# ETH_CAN_Sheet1.net
KiCad netlist of a schematic drawn in Altium Designer
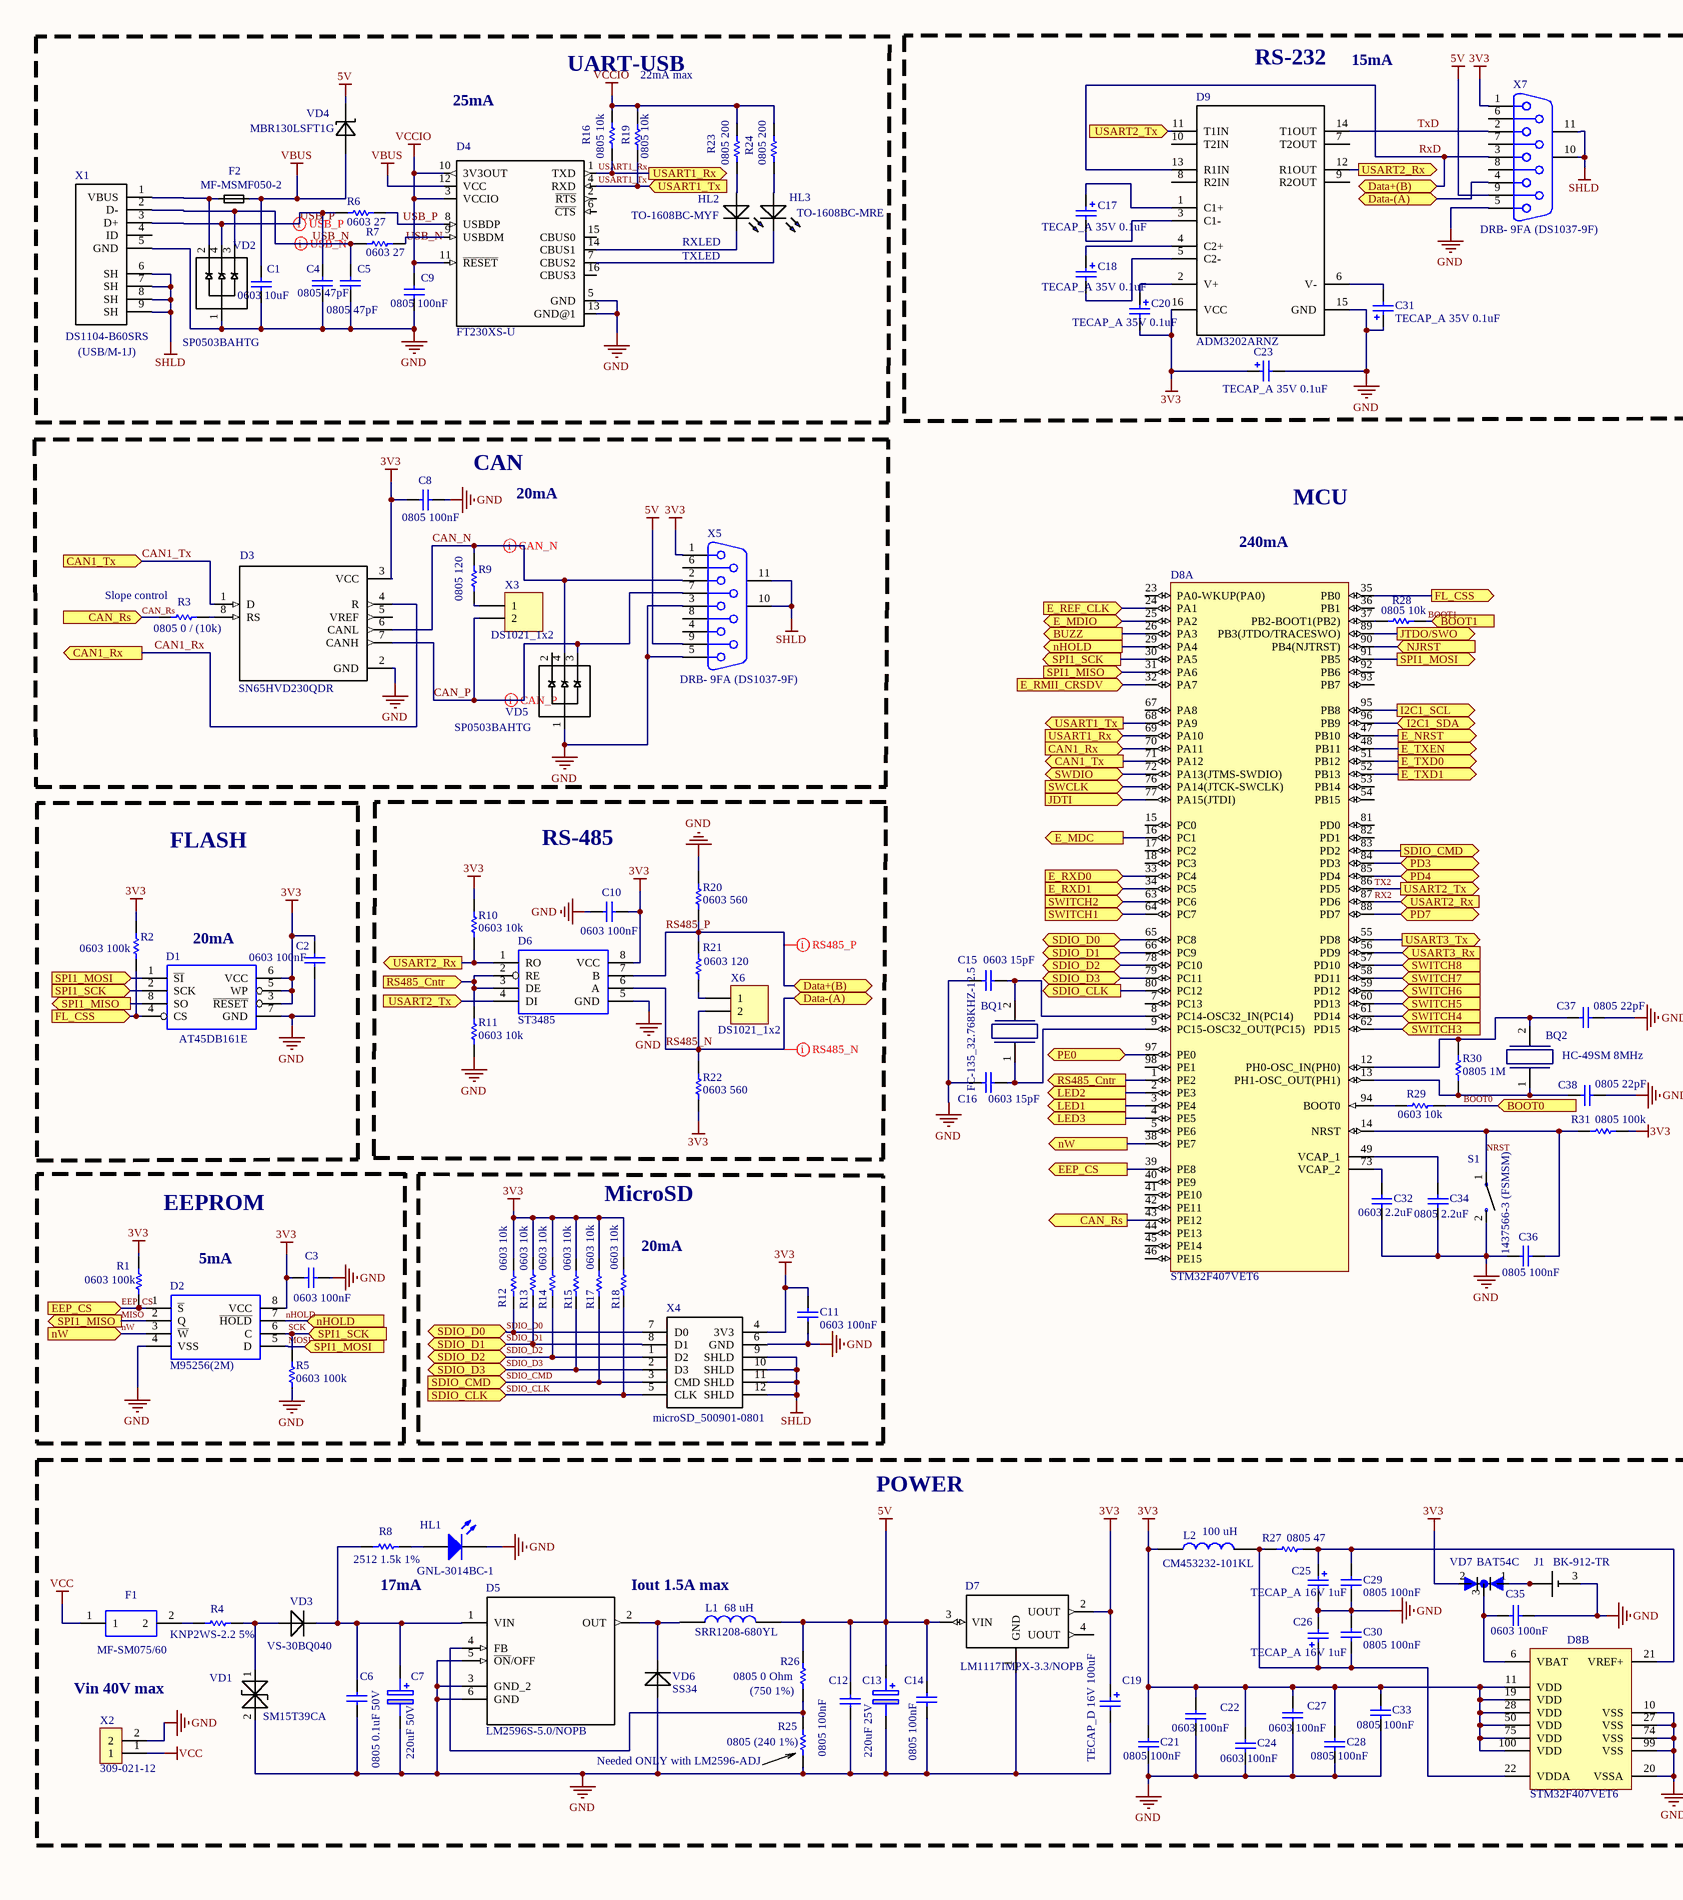
[diagram p0: ETH_CAN_Sheet1.SchDoc, left]
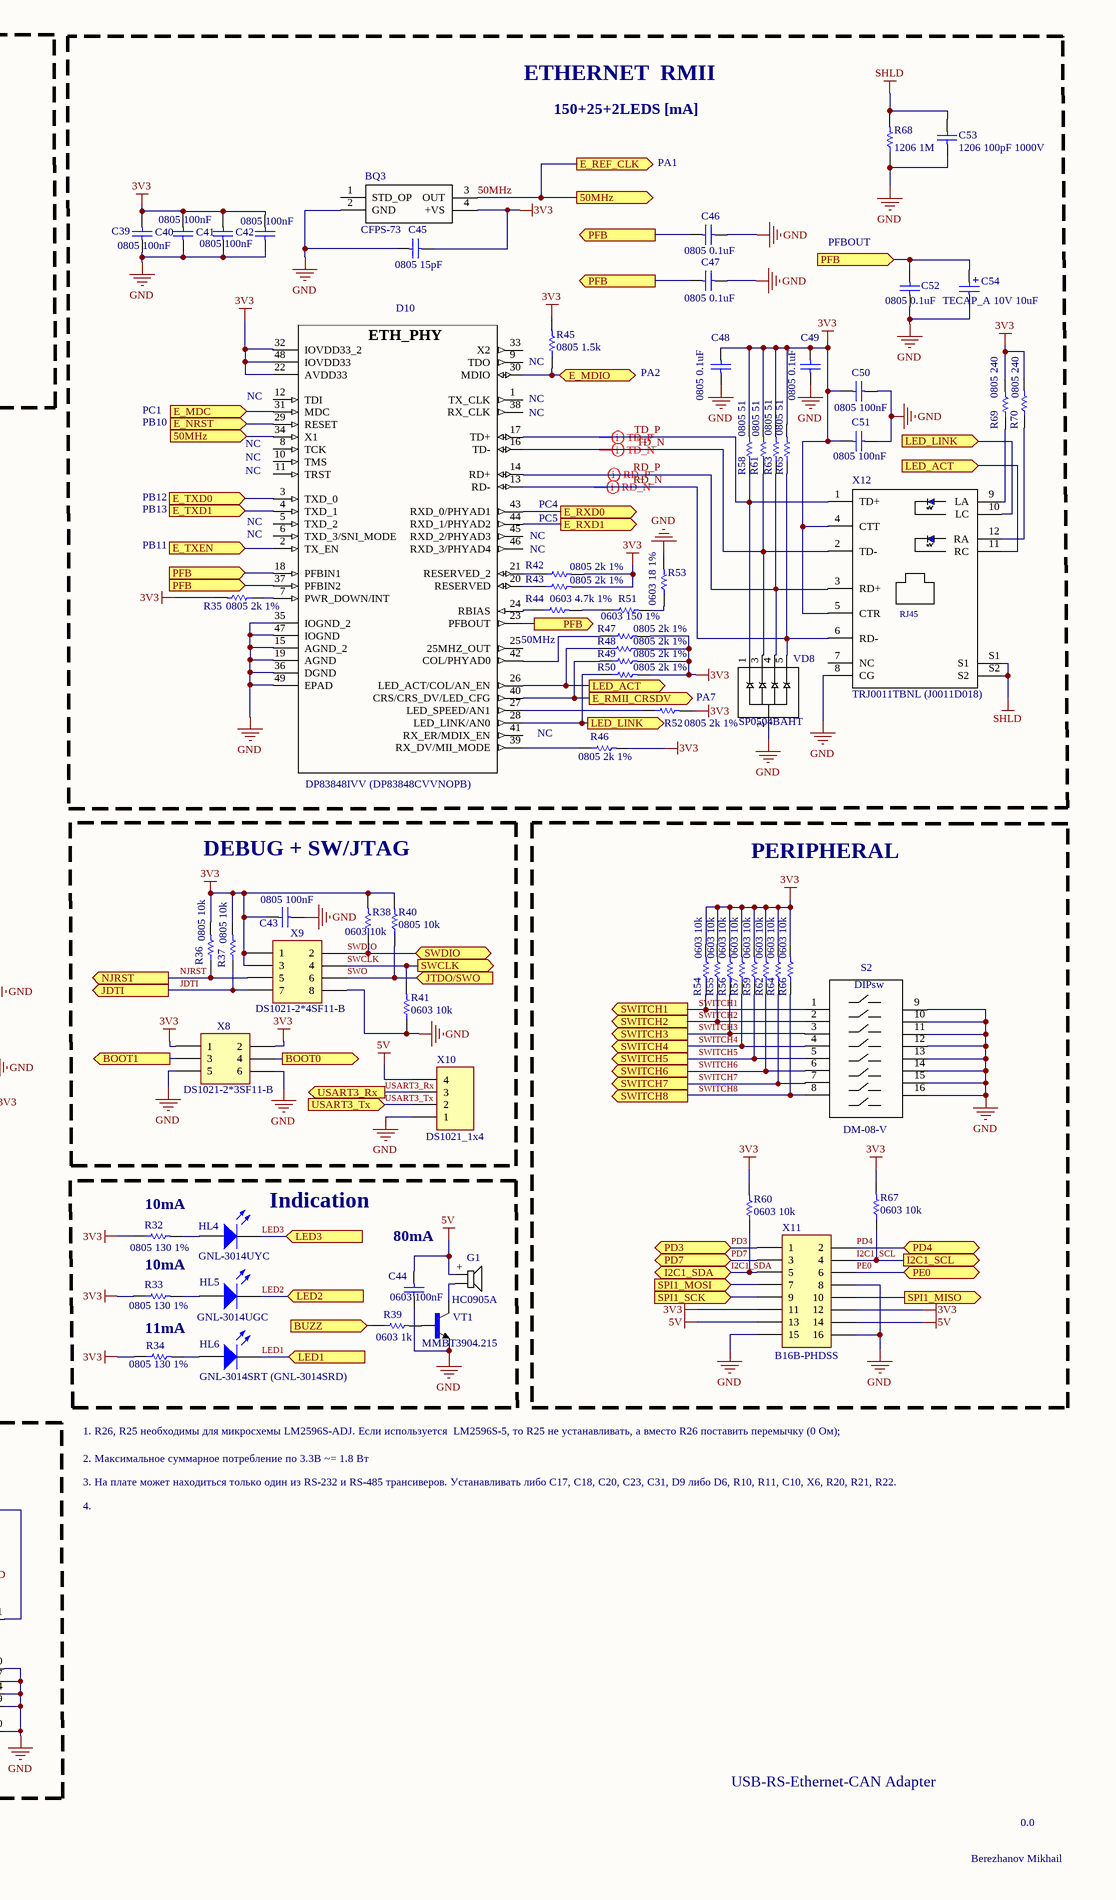
[diagram p1: ETH_CAN_Sheet1.SchDoc, right]

(export (version "E")
  (design (tool "Eeschema 10.0.6"))
  (components
    (comp (ref "BQ1")
      (value "FC-135_32.768KHZ-12.5")
      (footprint "FC-135")
      (description "Clock SMD Crystal")
      (libsource (lib "MyCompLib") (part "FC135-32768-7"))
    )
    (comp (ref "BQ2")
      (value "HC-49SM 8MHz")
      (footprint "HC49SM")
      (description "HC49SM")
      (libsource (lib "MyCompLib") (part "HC49SM"))
    )
    (comp (ref "BQ3")
      (value "CFPS-73")
      (footprint "CFPS-73")
      (description "IQD FREQUENCY PRODUCTS - SPXO018044-CFPS-73 - OSCILLATOR FREQUENCY, 50MHZ")
      (libsource (lib "MyCompLib") (part "SPXO018044CFPS-73"))
    )
    (comp (ref "C1")
      (value "0603 10uF")
      (footprint "C_SMD0603")
      (description "SMD Cap 0603")
      (libsource (lib "MyCompLib") (part "C0603"))
    )
    (comp (ref "C2")
      (value "0603 100nF")
      (footprint "C_SMD0603")
      (description "SMD Cap 0603")
      (libsource (lib "MyCompLib") (part "C0603"))
    )
    (comp (ref "C3")
      (value "0603 100nF")
      (footprint "C_SMD0603")
      (description "SMD Cap 0603")
      (libsource (lib "MyCompLib") (part "C0603"))
    )
    (comp (ref "C4")
      (value "0805 47pF")
      (footprint "C_SMD0805")
      (description "SMD Cap 0805")
      (fields (field (name "PUBLISHER") "Altium Limited"))
      (libsource (lib "MyCompLib") (part "C0805"))
    )
    (comp (ref "C5")
      (value "0805 47pF")
      (footprint "C_SMD0805")
      (description "SMD Cap 0805")
      (fields (field (name "PUBLISHER") "Altium Limited"))
      (libsource (lib "MyCompLib") (part "C0805"))
    )
    (comp (ref "C6")
      (value "0805 0.1uF 50V")
      (footprint "C_SMD0805")
      (description "SMD Cap 0805")
      (fields (field (name "PUBLISHER") "Altium Limited"))
      (libsource (lib "MyCompLib") (part "C0805"))
    )
    (comp (ref "C7")
      (value "220uF 50V")
      (footprint "SMD_ELC_CAP")
      (fields
        (field (name "MANUFACTURER_PART_NUMBER") "EEEFK1H221P")
        (field (name "RS PART NUMBER") "6294598")
      )
      (libsource (lib "MyCompLib") (part "EEEFK1H221P"))
    )
    (comp (ref "C8")
      (value "0805 100nF")
      (footprint "C_SMD0805")
      (description "SMD Cap 0805")
      (fields (field (name "PUBLISHER") "Altium Limited"))
      (libsource (lib "MyCompLib") (part "C0805"))
    )
    (comp (ref "C9")
      (value "0805 100nF")
      (footprint "C_SMD0805")
      (description "SMD Cap 0805")
      (fields (field (name "PUBLISHER") "Altium Limited"))
      (libsource (lib "MyCompLib") (part "C0805"))
    )
    (comp (ref "C10")
      (value "0603 100nF")
      (footprint "C_SMD0603")
      (description "SMD Cap 0603")
      (libsource (lib "MyCompLib") (part "C0603"))
    )
    (comp (ref "C11")
      (value "0603 100nF")
      (footprint "C_SMD0603")
      (description "SMD Cap 0603")
      (libsource (lib "MyCompLib") (part "C0603"))
    )
    (comp (ref "C12")
      (value "0805 100nF")
      (footprint "C_SMD0805")
      (description "SMD Cap 0805")
      (fields (field (name "PUBLISHER") "Altium Limited"))
      (libsource (lib "MyCompLib") (part "C0805"))
    )
    (comp (ref "C13")
      (value "220uF 25V")
      (footprint "SMD_ELC_CAP")
      (fields
        (field (name "MANUFACTURER_PART_NUMBER") "EEEFK1H221P")
        (field (name "RS PART NUMBER") "6294598")
      )
      (libsource (lib "MyCompLib") (part "EEEFK1H221P"))
    )
    (comp (ref "C14")
      (value "0805 100nF")
      (footprint "C_SMD0805")
      (description "SMD Cap 0805")
      (libsource (lib "") (part "C0805_1"))
    )
    (comp (ref "C15")
      (value "0603 15pF")
      (footprint "C_SMD0603")
      (description "SMD Cap 0603")
      (libsource (lib "MyCompLib") (part "C0603"))
    )
    (comp (ref "C16")
      (value "0603 15pF")
      (footprint "C_SMD0603")
      (description "SMD Cap 0603")
      (libsource (lib "MyCompLib") (part "C0603"))
    )
    (comp (ref "C17")
      (value "TECAP_A 35V 0.1uF")
      (footprint "TECAP_A")
      (description "Tantalum pol cap type A")
      (libsource (lib "MyCompLib") (part "TECAP_A"))
    )
    (comp (ref "C18")
      (value "TECAP_A 35V 0.1uF")
      (footprint "TECAP_A")
      (description "Tantalum pol cap type A")
      (libsource (lib "MyCompLib") (part "TECAP_A"))
    )
    (comp (ref "C19")
      (value "TECAP_D 16V 100uF")
      (footprint "TECAP_D")
      (description "Tantalum pol cap type D")
      (libsource (lib "MyCompLib") (part "TECAP_D"))
    )
    (comp (ref "C20")
      (value "TECAP_A 35V 0.1uF")
      (footprint "TECAP_A")
      (description "Tantalum pol cap type A")
      (libsource (lib "MyCompLib") (part "TECAP_A"))
    )
    (comp (ref "C21")
      (value "0805 100nF")
      (footprint "C_SMD0805")
      (description "SMD Cap 0805")
      (fields (field (name "PUBLISHER") "Altium Limited"))
      (libsource (lib "MyCompLib") (part "C0805"))
    )
    (comp (ref "C22")
      (value "0603 100nF")
      (footprint "C_SMD0603")
      (description "SMD Cap 0603")
      (libsource (lib "MyCompLib") (part "C0603"))
    )
    (comp (ref "C23")
      (value "TECAP_A 35V 0.1uF")
      (footprint "TECAP_A")
      (description "Tantalum pol cap type A")
      (libsource (lib "MyCompLib") (part "TECAP_A"))
    )
    (comp (ref "C24")
      (value "0603 100nF")
      (footprint "C_SMD0603")
      (description "SMD Cap 0603")
      (libsource (lib "MyCompLib") (part "C0603"))
    )
    (comp (ref "C25")
      (value "TECAP_A 16V 1uF")
      (footprint "TECAP_A")
      (description "Tantalum pol cap type A")
      (libsource (lib "MyCompLib") (part "TECAP_A"))
    )
    (comp (ref "C26")
      (value "TECAP_A 16V 1uF")
      (footprint "TECAP_A")
      (description "Tantalum pol cap type A")
      (libsource (lib "MyCompLib") (part "TECAP_A"))
    )
    (comp (ref "C27")
      (value "0603 100nF")
      (footprint "C_SMD0603")
      (description "SMD Cap 0603")
      (libsource (lib "MyCompLib") (part "C0603"))
    )
    (comp (ref "C28")
      (value "0805 100nF")
      (footprint "C_SMD0805")
      (description "SMD Cap 0805")
      (fields (field (name "PUBLISHER") "Altium Limited"))
      (libsource (lib "MyCompLib") (part "C0805"))
    )
    (comp (ref "C29")
      (value "0805 100nF")
      (footprint "C_SMD0805")
      (description "SMD Cap 0805")
      (fields (field (name "PUBLISHER") "Altium Limited"))
      (libsource (lib "MyCompLib") (part "C0805"))
    )
    (comp (ref "C30")
      (value "0805 100nF")
      (footprint "C_SMD0805")
      (description "SMD Cap 0805")
      (fields (field (name "PUBLISHER") "Altium Limited"))
      (libsource (lib "MyCompLib") (part "C0805"))
    )
    (comp (ref "C31")
      (value "TECAP_A 35V 0.1uF")
      (footprint "TECAP_A")
      (description "Tantalum pol cap type A")
      (libsource (lib "MyCompLib") (part "TECAP_A"))
    )
    (comp (ref "C32")
      (value "0603 2.2uF")
      (footprint "C_SMD0603")
      (description "SMD Cap 0603")
      (libsource (lib "MyCompLib") (part "C0603"))
    )
    (comp (ref "C33")
      (value "0805 100nF")
      (footprint "C_SMD0805")
      (description "SMD Cap 0805")
      (fields (field (name "PUBLISHER") "Altium Limited"))
      (libsource (lib "MyCompLib") (part "C0805"))
    )
    (comp (ref "C34")
      (value "0805 2.2uF")
      (footprint "C_SMD0805")
      (description "SMD Cap 0805")
      (fields (field (name "PUBLISHER") "Altium Limited"))
      (libsource (lib "MyCompLib") (part "C0805"))
    )
    (comp (ref "C35")
      (value "0603 100nF")
      (footprint "C_SMD0603")
      (description "SMD Cap 0603")
      (libsource (lib "MyCompLib") (part "C0603"))
    )
    (comp (ref "C36")
      (value "0805 100nF")
      (footprint "C_SMD0805")
      (description "SMD Cap 0805")
      (fields (field (name "PUBLISHER") "Altium Limited"))
      (libsource (lib "MyCompLib") (part "C0805"))
    )
    (comp (ref "C37")
      (value "0805 22pF")
      (footprint "C_SMD0805")
      (description "SMD Cap 0805")
      (fields (field (name "PUBLISHER") "Altium Limited"))
      (libsource (lib "MyCompLib") (part "C0805"))
    )
    (comp (ref "C38")
      (value "0805 22pF")
      (footprint "C_SMD0805")
      (description "SMD Cap 0805")
      (fields (field (name "PUBLISHER") "Altium Limited"))
      (libsource (lib "MyCompLib") (part "C0805"))
    )
    (comp (ref "C39")
      (value "0805 100nF")
      (footprint "C_SMD0805")
      (description "SMD Cap 0805")
      (fields (field (name "PUBLISHER") "Altium Limited"))
      (libsource (lib "MyCompLib") (part "C0805"))
    )
    (comp (ref "C40")
      (value "0805 100nF")
      (footprint "C_SMD0805")
      (description "SMD Cap 0805")
      (fields (field (name "PUBLISHER") "Altium Limited"))
      (libsource (lib "MyCompLib") (part "C0805"))
    )
    (comp (ref "C41")
      (value "0805 100nF")
      (footprint "C_SMD0805")
      (description "SMD Cap 0805")
      (fields (field (name "PUBLISHER") "Altium Limited"))
      (libsource (lib "MyCompLib") (part "C0805"))
    )
    (comp (ref "C42")
      (value "0805 100nF")
      (footprint "C_SMD0805")
      (description "SMD Cap 0805")
      (fields (field (name "PUBLISHER") "Altium Limited"))
      (libsource (lib "MyCompLib") (part "C0805"))
    )
    (comp (ref "C43")
      (value "0805 100nF")
      (footprint "C_SMD0805")
      (description "SMD Cap 0805")
      (fields (field (name "PUBLISHER") "Altium Limited"))
      (libsource (lib "MyCompLib") (part "C0805"))
    )
    (comp (ref "C44")
      (value "0603 100nF")
      (footprint "C_SMD0603")
      (description "SMD Cap 0603")
      (libsource (lib "MyCompLib") (part "C0603"))
    )
    (comp (ref "C45")
      (value "0805 15pF")
      (footprint "C_SMD0805")
      (description "SMD Cap 0805")
      (fields (field (name "PUBLISHER") "Altium Limited"))
      (libsource (lib "MyCompLib") (part "C0805"))
    )
    (comp (ref "C46")
      (value "0805 0.1uF")
      (footprint "C_SMD0805")
      (description "SMD Cap 0805")
      (fields (field (name "PUBLISHER") "Altium Limited"))
      (libsource (lib "MyCompLib") (part "C0805"))
    )
    (comp (ref "C47")
      (value "0805 0.1uF")
      (footprint "C_SMD0805")
      (description "SMD Cap 0805")
      (fields (field (name "PUBLISHER") "Altium Limited"))
      (libsource (lib "MyCompLib") (part "C0805"))
    )
    (comp (ref "C48")
      (value "0805 0.1uF")
      (footprint "C_SMD0805")
      (description "SMD Cap 0805")
      (fields (field (name "PUBLISHER") "Altium Limited"))
      (libsource (lib "MyCompLib") (part "C0805"))
    )
    (comp (ref "C49")
      (value "0805 0.1uF")
      (footprint "C_SMD0805")
      (description "SMD Cap 0805")
      (fields (field (name "PUBLISHER") "Altium Limited"))
      (libsource (lib "MyCompLib") (part "C0805"))
    )
    (comp (ref "C50")
      (value "0805 100nF")
      (footprint "C_SMD0805")
      (description "SMD Cap 0805")
      (fields (field (name "PUBLISHER") "Altium Limited"))
      (libsource (lib "MyCompLib") (part "C0805"))
    )
    (comp (ref "C51")
      (value "0805 100nF")
      (footprint "C_SMD0805")
      (description "SMD Cap 0805")
      (fields (field (name "PUBLISHER") "Altium Limited"))
      (libsource (lib "MyCompLib") (part "C0805"))
    )
    (comp (ref "C52")
      (value "0805 0.1uF")
      (footprint "C_SMD0805")
      (description "SMD Cap 0805")
      (fields (field (name "PUBLISHER") "Altium Limited"))
      (libsource (lib "MyCompLib") (part "C0805"))
    )
    (comp (ref "C53")
      (value "1206 100pF 1000V")
      (footprint "CAP SMD1206")
      (description "SMD Cap 1206")
      (fields (field (name "PUBLISHER") "Altium Limited"))
      (libsource (lib "MyCompLib") (part "C1206"))
    )
    (comp (ref "C54")
      (value "TECAP_A 10V 10uF")
      (footprint "TECAP_A")
      (description "Tantalum pol cap type A")
      (libsource (lib "MyCompLib") (part "TECAP_A"))
    )
    (comp (ref "D1")
      (value "AT45DB161E")
      (footprint "SOIC8(5.3mm)")
      (description "SPI FLASH 16Mbit(528 bytes x 4096 pages)")
      (libsource (lib "MyCompLib") (part "AT45DB161E"))
    )
    (comp (ref "D2")
      (value "M95256(2M)")
      (footprint "SOIC8 (SO-8)")
      (description "M95256-WMN6TP, Serial EEPROM Memory 256kbit, Serial-SPI, 60ns 2.5  5.5 V, 8-Pin SOIC")
      (libsource (lib "MyCompLib") (part "M95256(2M)-WMN6TP"))
    )
    (comp (ref "D3")
      (value "SN65HVD230QDR")
      (footprint "SOIC-12")
      (description "3.3-V CAN Transceiver with Standby Mode 8-SOIC -40 to 125")
      (fields (field (name "MF") "Texas Instruments"))
      (libsource (lib "MyCompLib") (part "SN65HVD230QDR"))
    )
    (comp (ref "D4")
      (value "FT230XS-U")
      (footprint "SSOP16")
      (description "FT230XS-U, USB Controller, 3MBd, USB 1.1, USB 2.0, 5 V, 16-Pin SSOP")
      (fields (field (name "MF") "FTDI,"))
      (libsource (lib "MyCompLib") (part "FT230XS-U"))
    )
    (comp (ref "D5")
      (value "LM2596S-5.0/NOPB")
      (footprint "TO263-5")
      (description "SIMPLE SWITCHER&#174; 4.5V to 40V, 3A Low Component Count Step-Down Regulator")
      (libsource (lib "MyCompLib") (part "LM2596S"))
    )
    (comp (ref "D6")
      (value "ST3485")
      (footprint "SOIC8 (SO-8)")
      (description "3.3 V low power transceiver for RS-485")
      (libsource (lib "MyCompLib") (part "ST3485"))
    )
    (comp (ref "D7")
      (value "LM1117IMPX-3.3/NOPB")
      (footprint "SOT223")
      (description "Линейный регулятор с низким падением напряжения, 3.3В")
      (libsource (lib "MyCompLib") (part "LM1117-3.3"))
    )
    (comp (ref "D8")
      (value "STM32F407VET6")
      (footprint "STM-LQFP100_N")
      (fields (field (name "MANUFACTURER") "STMicroelectronics"))
      (libsource (lib "STMicroelectronics STM32 F4") (part "STM32F407VET6"))
    )
    (comp (ref "D9")
      (value "ADM3202ARNZ")
      (footprint "SOIC-16")
      (description "3.3V SMD RS232-UART")
      (libsource (lib "MyCompLib") (part "ADM3202ARNZ"))
    )
    (comp (ref "D10")
      (value "DP83848IVV (DP83848CVVNOPB)")
      (footprint "QFP48")
      (description "ETH Transciever")
      (libsource (lib "MyCompLib") (part "DP83848CVVNOPB"))
    )
    (comp (ref "F1")
      (value "MF-SM075/60")
      (footprint "MF-SM075/60")
      (libsource (lib "MyCompLib") (part "MF-SM075/60"))
    )
    (comp (ref "F2")
      (value "MF-MSMF050-2")
      (footprint "FUSE1812x0")
      (description "PTC Resettable Fuse 0.5A_hold_ 1A_trip_ 15V 100A 0.8W 0.15s 0.15Ohm SMD Solder Pad 1812 T/R")
      (libsource (lib "MyCompLib") (part "MF-MSMF050-2"))
    )
    (comp (ref "G1")
      (value "HC0905A")
      (footprint "HC090xA")
      (description "Buzzer 5V 80mA h=5mm d=9.5mm 3200Hz")
      (libsource (lib "MyCompLib") (part "HC0905A"))
    )
    (comp (ref "HL1")
      (value "GNL-3014BC-1")
      (footprint "LED3mm")
      (libsource (lib "MyCompLib") (part "LED_0_25_4"))
    )
    (comp (ref "HL2")
      (value "TO-1608BC-MYF")
      (footprint "LED_SMD1608GREEN")
      (description "TO-1608BC-BF \\  TO-1608BC-MRE")
      (libsource (lib "MyCompLib") (part "LED_SMD"))
    )
    (comp (ref "HL3")
      (value "TO-1608BC-MRE")
      (footprint "LED_SMD1608")
      (description "TO-1608BC-BF \\  TO-1608BC-MRE")
      (libsource (lib "MyCompLib") (part "LED_SMD"))
    )
    (comp (ref "HL4")
      (value "GNL-3014UYC")
      (footprint "LED3mm")
      (description "Светодиод желтый 25° d=3мм 1000мКд 589нМ (Yellow)")
      (libsource (lib "MyCompLib") (part "LED_0_25_4"))
    )
    (comp (ref "HL5")
      (value "GNL-3014UGC")
      (footprint "LED3mm")
      (description "Светодиод зеленый 25° d=3мм 1200мКд 572нМ (Green)")
      (libsource (lib "MyCompLib") (part "LED_0_25_4"))
    )
    (comp (ref "HL6")
      (value "GNL-3014SRT (GNL-3014SRD)")
      (footprint "LED3mm")
      (description "Светодиод красный 20° d=3мм 200мКд 660нМ (Red)")
      (libsource (lib "MyCompLib") (part "LED_0_25_4"))
    )
    (comp (ref "J1")
      (value "BK-912-TR")
      (footprint "BK-912-TR")
      (description "Holder Coin Cell 20mm Smd")
      (libsource (lib "MyCompLib") (part "BK-912-TR"))
    )
    (comp (ref "L1")
      (value "SRR1208-680YL")
      (footprint "SRR1208")
      (description "Fixed Inductors 330uH 10% SMD 1208")
      (fields (field (name "MANUFACTURER_PART_NUMBER") "SRR1208-682KL"))
      (libsource (lib "MyCompLib") (part "SRR1208-682KL"))
    )
    (comp (ref "L2")
      (value "CM453232-101KL")
      (footprint "CM453232-101KL")
      (description "BOURNS - CM453232-101KL - INDUCTOR, 4532 CASE, 100UH")
      (fields
        (field (name "MANUFACTURER_PART_NUMBER") "CM453232-471KL")
        (field (name "RS PART NUMBER") "6934353")
      )
      (libsource (lib "MyCompLib") (part "CM453232-471KL"))
    )
    (comp (ref "R1")
      (value "0603 100k")
      (footprint "R_SMD0603")
      (description "SMD Res 0603")
      (libsource (lib "MyCompLib") (part "R0603"))
    )
    (comp (ref "R2")
      (value "0603 100k")
      (footprint "R_SMD0603")
      (description "SMD Res 0603")
      (libsource (lib "MyCompLib") (part "R0603"))
    )
    (comp (ref "R3")
      (value "0805 0 / (10k)")
      (footprint "R_SMD0805")
      (description "SMD Res 0805")
      (libsource (lib "MyCompLib") (part "R0805"))
    )
    (comp (ref "R4")
      (value "KNP2WS-2.2 5%")
      (footprint "KNP2WS")
      (description "Резисторы с проволочной обмоткой – сквозное отверстие 2.2ohm 2W 5%")
      (libsource (lib "MyCompLib") (part "KNP2WS"))
    )
    (comp (ref "R5")
      (value "0603 100k")
      (footprint "R_SMD0603")
      (description "SMD Res 0603")
      (libsource (lib "MyCompLib") (part "R0603"))
    )
    (comp (ref "R6")
      (value "0603 27")
      (footprint "R_SMD0603")
      (description "SMD Res 0603")
      (libsource (lib "MyCompLib") (part "R0603"))
    )
    (comp (ref "R7")
      (value "0603 27")
      (footprint "R_SMD0603")
      (description "SMD Res 0603")
      (libsource (lib "MyCompLib") (part "R0603"))
    )
    (comp (ref "R8")
      (value "2512 1.5k 1%")
      (footprint "R_SMD2512")
      (description "SMD Res 2512")
      (libsource (lib "MyCompLib") (part "R2512"))
    )
    (comp (ref "R9")
      (value "0805 120")
      (footprint "R_SMD0805")
      (description "SMD Res 0805")
      (libsource (lib "MyCompLib") (part "R0805"))
    )
    (comp (ref "R10")
      (value "0603 10k")
      (footprint "R_SMD0603")
      (description "SMD Res 0603")
      (libsource (lib "MyCompLib") (part "R0603"))
    )
    (comp (ref "R11")
      (value "0603 10k")
      (footprint "R_SMD0603")
      (description "SMD Res 0603")
      (libsource (lib "MyCompLib") (part "R0603"))
    )
    (comp (ref "R12")
      (value "0603 10k")
      (footprint "R_SMD0603")
      (description "SMD Res 0603")
      (libsource (lib "MyCompLib") (part "R0603"))
    )
    (comp (ref "R13")
      (value "0603 10k")
      (footprint "R_SMD0603")
      (description "SMD Res 0603")
      (libsource (lib "MyCompLib") (part "R0603"))
    )
    (comp (ref "R14")
      (value "0603 10k")
      (footprint "R_SMD0603")
      (description "SMD Res 0603")
      (libsource (lib "MyCompLib") (part "R0603"))
    )
    (comp (ref "R15")
      (value "0603 10k")
      (footprint "R_SMD0603")
      (description "SMD Res 0603")
      (libsource (lib "MyCompLib") (part "R0603"))
    )
    (comp (ref "R16")
      (value "0805 10k")
      (footprint "R_SMD0805")
      (description "SMD Res 0805")
      (libsource (lib "MyCompLib") (part "R0805"))
    )
    (comp (ref "R17")
      (value "0603 10k")
      (footprint "R_SMD0603")
      (description "SMD Res 0603")
      (libsource (lib "MyCompLib") (part "R0603"))
    )
    (comp (ref "R18")
      (value "0603 10k")
      (footprint "R_SMD0603")
      (description "SMD Res 0603")
      (libsource (lib "MyCompLib") (part "R0603"))
    )
    (comp (ref "R19")
      (value "0805 10k")
      (footprint "R_SMD0805")
      (description "SMD Res 0805")
      (libsource (lib "MyCompLib") (part "R0805"))
    )
    (comp (ref "R20")
      (value "0603 560")
      (footprint "R_SMD0603")
      (description "SMD Res 0603")
      (libsource (lib "MyCompLib") (part "R0603"))
    )
    (comp (ref "R21")
      (value "0603 120")
      (footprint "R_SMD0603")
      (description "SMD Res 0603")
      (libsource (lib "MyCompLib") (part "R0603"))
    )
    (comp (ref "R22")
      (value "0603 560")
      (footprint "R_SMD0603")
      (description "SMD Res 0603")
      (libsource (lib "MyCompLib") (part "R0603"))
    )
    (comp (ref "R23")
      (value "0805 200")
      (footprint "R_SMD0805")
      (description "SMD Res 0805")
      (libsource (lib "MyCompLib") (part "R0805"))
    )
    (comp (ref "R24")
      (value "0805 200")
      (footprint "R_SMD0805")
      (description "SMD Res 0805")
      (libsource (lib "MyCompLib") (part "R0805"))
    )
    (comp (ref "R25")
      (value "0805 (240 1%)")
      (footprint "R_SMD0805")
      (description "SMD Res 0805")
      (libsource (lib "MyCompLib") (part "R0805"))
    )
    (comp (ref "R26")
      (value "0805 0 Ohm")
      (footprint "C_SMD0805")
      (description "SMD Res 0805")
      (libsource (lib "MyCompLib") (part "R0805"))
    )
    (comp (ref "R27")
      (value "0805 47")
      (footprint "R_SMD0805")
      (description "SMD Res 0805")
      (libsource (lib "MyCompLib") (part "R0805"))
    )
    (comp (ref "R28")
      (value "0805 10k")
      (footprint "R_SMD0805")
      (description "SMD Res 0805")
      (libsource (lib "MyCompLib") (part "R0805"))
    )
    (comp (ref "R29")
      (value "0603 10k")
      (footprint "R_SMD0603")
      (description "SMD Res 0603")
      (libsource (lib "MyCompLib") (part "R0603"))
    )
    (comp (ref "R30")
      (value "0805 1M")
      (footprint "R_SMD0805")
      (description "SMD Res 0805")
      (libsource (lib "MyCompLib") (part "R0805"))
    )
    (comp (ref "R31")
      (value "0805 100k")
      (footprint "C_SMD0805")
      (description "SMD Res 0805")
      (libsource (lib "MyCompLib") (part "R0805"))
    )
    (comp (ref "R32")
      (value "0805 130 1%")
      (footprint "R_SMD0805")
      (description "SMD Res 0805")
      (libsource (lib "MyCompLib") (part "R0805"))
    )
    (comp (ref "R33")
      (value "0805 130 1%")
      (footprint "R_SMD0805")
      (description "SMD Res 0805")
      (libsource (lib "MyCompLib") (part "R0805"))
    )
    (comp (ref "R34")
      (value "0805 130 1%")
      (footprint "R_SMD0805")
      (description "SMD Res 0805")
      (libsource (lib "MyCompLib") (part "R0805"))
    )
    (comp (ref "R35")
      (value "0805 2k 1%")
      (footprint "R_SMD0805")
      (description "SMD Res 0805")
      (libsource (lib "MyCompLib") (part "R0805"))
    )
    (comp (ref "R36")
      (value "0805 10k")
      (footprint "R_SMD0805")
      (description "SMD Res 0805")
      (libsource (lib "MyCompLib") (part "R0805"))
    )
    (comp (ref "R37")
      (value "0805 10k")
      (footprint "R_SMD0805")
      (description "SMD Res 0805")
      (libsource (lib "MyCompLib") (part "R0805"))
    )
    (comp (ref "R38")
      (value "0603 10k")
      (footprint "R_SMD0603")
      (description "SMD Res 0603")
      (libsource (lib "MyCompLib") (part "R0603"))
    )
    (comp (ref "R39")
      (value "0603 1k")
      (footprint "R_SMD0603")
      (description "SMD Res 0603")
      (libsource (lib "MyCompLib") (part "R0603"))
    )
    (comp (ref "R40")
      (value "0805 10k")
      (footprint "R_SMD0805")
      (description "SMD Res 0805")
      (libsource (lib "MyCompLib") (part "R0805"))
    )
    (comp (ref "R41")
      (value "0603 10k")
      (footprint "R_SMD0603")
      (description "SMD Res 0603")
      (libsource (lib "MyCompLib") (part "R0603"))
    )
    (comp (ref "R42")
      (value "0805 2k 1%")
      (footprint "R_SMD0805")
      (description "SMD Res 0805")
      (libsource (lib "MyCompLib") (part "R0805"))
    )
    (comp (ref "R43")
      (value "0805 2k 1%")
      (footprint "R_SMD0805")
      (description "SMD Res 0805")
      (libsource (lib "MyCompLib") (part "R0805"))
    )
    (comp (ref "R44")
      (value "0603 4.7k 1%")
      (footprint "R_SMD0603")
      (description "SMD Res 0603")
      (libsource (lib "MyCompLib") (part "R0603"))
    )
    (comp (ref "R45")
      (value "0805 1.5k")
      (footprint "R_SMD0805")
      (description "SMD Res 0805")
      (libsource (lib "MyCompLib") (part "R0805"))
    )
    (comp (ref "R46")
      (value "0805 2k 1%")
      (footprint "R_SMD0805")
      (description "SMD Res 0805")
      (libsource (lib "MyCompLib") (part "R0805"))
    )
    (comp (ref "R47")
      (value "0805 2k 1%")
      (footprint "R_SMD0805")
      (description "SMD Res 0805")
      (libsource (lib "MyCompLib") (part "R0805"))
    )
    (comp (ref "R48")
      (value "0805 2k 1%")
      (footprint "R_SMD0805")
      (description "SMD Res 0805")
      (libsource (lib "MyCompLib") (part "R0805"))
    )
    (comp (ref "R49")
      (value "0805 2k 1%")
      (footprint "R_SMD0805")
      (description "SMD Res 0805")
      (libsource (lib "MyCompLib") (part "R0805"))
    )
    (comp (ref "R50")
      (value "0805 2k 1%")
      (footprint "R_SMD0805")
      (description "SMD Res 0805")
      (libsource (lib "MyCompLib") (part "R0805"))
    )
    (comp (ref "R51")
      (value "0603 150 1%")
      (footprint "R_SMD0603")
      (description "SMD Res 0603")
      (libsource (lib "MyCompLib") (part "R0603"))
    )
    (comp (ref "R52")
      (value "0805 2k 1%")
      (footprint "R_SMD0805")
      (description "SMD Res 0805")
      (libsource (lib "MyCompLib") (part "R0805"))
    )
    (comp (ref "R53")
      (value "0603 18 1%")
      (footprint "R_SMD0603")
      (description "SMD Res 0603")
      (libsource (lib "MyCompLib") (part "R0603"))
    )
    (comp (ref "R54")
      (value "0603 10k")
      (footprint "R_SMD0603")
      (description "SMD Res 0603")
      (libsource (lib "MyCompLib") (part "R0603"))
    )
    (comp (ref "R55")
      (value "0603 10k")
      (footprint "R_SMD0603")
      (description "SMD Res 0603")
      (libsource (lib "MyCompLib") (part "R0603"))
    )
    (comp (ref "R56")
      (value "0603 10k")
      (footprint "R_SMD0603")
      (description "SMD Res 0603")
      (libsource (lib "MyCompLib") (part "R0603"))
    )
    (comp (ref "R57")
      (value "0603 10k")
      (footprint "R_SMD0603")
      (description "SMD Res 0603")
      (libsource (lib "MyCompLib") (part "R0603"))
    )
    (comp (ref "R58")
      (value "0805 51")
      (footprint "R_SMD0805")
      (description "SMD Res 0805")
      (libsource (lib "MyCompLib") (part "R0805"))
    )
    (comp (ref "R59")
      (value "0603 10k")
      (footprint "R_SMD0603")
      (description "SMD Res 0603")
      (libsource (lib "MyCompLib") (part "R0603"))
    )
    (comp (ref "R60")
      (value "0603 10k")
      (footprint "R_SMD0603")
      (description "SMD Res 0603")
      (libsource (lib "MyCompLib") (part "R0603"))
    )
    (comp (ref "R61")
      (value "0805 51")
      (footprint "R_SMD0805")
      (description "SMD Res 0805")
      (libsource (lib "MyCompLib") (part "R0805"))
    )
    (comp (ref "R62")
      (value "0603 10k")
      (footprint "R_SMD0603")
      (description "SMD Res 0603")
      (libsource (lib "MyCompLib") (part "R0603"))
    )
    (comp (ref "R63")
      (value "0805 51")
      (footprint "R_SMD0805")
      (description "SMD Res 0805")
      (libsource (lib "MyCompLib") (part "R0805"))
    )
    (comp (ref "R64")
      (value "0603 10k")
      (footprint "R_SMD0603")
      (description "SMD Res 0603")
      (libsource (lib "MyCompLib") (part "R0603"))
    )
    (comp (ref "R65")
      (value "0805 51")
      (footprint "R_SMD0805")
      (description "SMD Res 0805")
      (libsource (lib "MyCompLib") (part "R0805"))
    )
    (comp (ref "R66")
      (value "0603 10k")
      (footprint "R_SMD0603")
      (description "SMD Res 0603")
      (libsource (lib "MyCompLib") (part "R0603"))
    )
    (comp (ref "R67")
      (value "0603 10k")
      (footprint "R_SMD0603")
      (description "SMD Res 0603")
      (libsource (lib "MyCompLib") (part "R0603"))
    )
    (comp (ref "R68")
      (value "1206 1M")
      (footprint "R_SMD1206")
      (description "SMD Res 1206")
      (libsource (lib "MyCompLib") (part "R1206"))
    )
    (comp (ref "R69")
      (value "0805 240")
      (footprint "R_SMD0805")
      (description "SMD Res 0805")
      (libsource (lib "MyCompLib") (part "R0805"))
    )
    (comp (ref "R70")
      (value "0805 240")
      (footprint "R_SMD0805")
      (description "SMD Res 0805")
      (libsource (lib "MyCompLib") (part "R0805"))
    )
    (comp (ref "S1")
      (value "1437566-3 (FSMSM)")
      (footprint "1437566-3")
      (description "FSMSM=3.5X6 SMT TACT")
      (fields (field (name "MP") "1437566-3") (field (name "MF") "TE Connectivity"))
      (libsource (lib "MyCompLib") (part "1437566-3"))
    )
    (comp (ref "S2")
      (value "DM-08-V")
      (footprint "DM-08-V")
      (description "SMD DIPSWITCH8")
      (libsource (lib "MyCompLib") (part "DM-08-V"))
    )
    (comp (ref "VD1")
      (value "SM15T39CA")
      (footprint "DO214AB SMC")
      (description "TVS Diode Bi-Directional SM15T39CA 69.7V, 1500W, SMC 2-Pin")
      (libsource (lib "MyCompLib") (part "SM15T39CA"))
    )
    (comp (ref "VD2")
      (value "SP0503BAHTG")
      (footprint "SP0503BAHTG")
      (description "SP050xBA Series 8 V 30 pF Uni-Directional SMT TVS Avalanche Diode Array SOT-143")
      (fields (field (name "MF") "Littelfuse Inc."))
      (libsource (lib "MyCompLib") (part "SP0503BAHTG"))
    )
    (comp (ref "VD3")
      (value "VS-30BQ040")
      (footprint "DO214AB SMC")
      (description "VS-30BQ040-M3/9AT Vishay VS-30BQ040-M3/9AT, SMT Schottky Diode, 40V 4A, 2-Pin DO-214AB")
      (libsource (lib "MyCompLib") (part "VS-30BQ040"))
    )
    (comp (ref "VD4")
      (value "MBR130LSFT1G")
      (footprint "SOD-123FL")
      (description "Schottky Barrier Diodes, 1A to 2A, ON Semiconductor")
      (libsource (lib "MyCompLib") (part "MBR130LSFT1G"))
    )
    (comp (ref "VD5")
      (value "SP0503BAHTG")
      (footprint "SP0503BAHTG")
      (description "SP050xBA Series 8 V 30 pF Uni-Directional SMT TVS Avalanche Diode Array SOT-143")
      (fields (field (name "MF") "Littelfuse Inc."))
      (libsource (lib "MyCompLib") (part "SP0503BAHTG"))
    )
    (comp (ref "VD6")
      (value "SS34")
      (footprint "DO214AB SMC")
      (description "Rectifier, Schottky; DO-214AB; 3.0A IF; 0.75V; 40V; 100A IFRM; 10000V/us; 1000pF")
      (libsource (lib "MyCompLib") (part "SS34"))
    )
    (comp (ref "VD7")
      (value "BAT54C")
      (footprint "BAT54C_SOT23-3")
      (description "Small Signal Schottky Diode, Dual Common Cathode, 30 V, 200 mA, 400 mV, 600 mA, 125 C")
      (libsource (lib "MyCompLib") (part "BAT54C"))
    )
    (comp (ref "VD8")
      (value "SP0504BAHT")
      (footprint "SOT23-5")
      (description "TVS Diode-4")
      (libsource (lib "MyCompLib") (part "SP0504BAHT"))
    )
    (comp (ref "VT1")
      (value "MMBT3904.215")
      (footprint "SOT23")
      (description "Транзистор NPN 40В 0.2А [SOT-23-3]")
      (libsource (lib "MyCompLib") (part "MMBT3904.215"))
    )
    (comp (ref "X1")
      (value "DS1104-B60SRS")
      (footprint "MUSB-05-S-B-SM")
      (description "Conn Mini USB 2.0 Type B RCP 5 POS 0.8mm Solder RA SMD 5 Terminal 1 Port Tray")
      (libsource (lib "MyCompLib") (part "MSUB-05 (DS1104)"))
    )
    (comp (ref "X2")
      (value "309-021-12")
      (footprint "390-021-12")
      (description "DG390-5.0-02P (XY118-2P-05) Зажимной Клеммник 2-контактный, 5.0мм угловой")
      (libsource (lib "MyCompLib") (part "309-021-12"))
    )
    (comp (ref "X3")
      (value "DS1021_1x2")
      (footprint "PLD2")
      (description "Вилка штыревая 2.54мм 1x2 прямая тип1")
      (libsource (lib "MyCompLib") (part "DS1021_1x2"))
    )
    (comp (ref "X4")
      (value "microSD_500901-0801")
      (footprint "5009001-0801")
      (description "TransFlash Memory Card,1.1mm hinge type TransFlash Memory Card,1.1mm hinge type")
      (libsource (lib "MyCompLib") (part "microSD_500901-0801"))
    )
    (comp (ref "X5")
      (value "DRB- 9FA (DS1037-9F)")
      (footprint "DRB- 9FA")
      (libsource (lib "MyCompLib") (part "DRB- 9FA (DS1037-9F)"))
    )
    (comp (ref "X6")
      (value "DS1021_1x2")
      (footprint "PLD2")
      (description "Вилка штыревая 2.54мм 1x2 прямая тип1")
      (libsource (lib "MyCompLib") (part "DS1021_1x2"))
    )
    (comp (ref "X7")
      (value "DRB- 9FA (DS1037-9F)")
      (footprint "DRB- 9FA")
      (libsource (lib "MyCompLib") (part "DRB- 9FA (DS1037-9F)"))
    )
    (comp (ref "X8")
      (value "DS1021-2*3SF11-B")
      (footprint "PLD2-3")
      (description "Вилка штыревая 2.54мм 2x3 прямая тип1")
      (libsource (lib "MyCompLib") (part "DS1021_2x3"))
    )
    (comp (ref "X9")
      (value "DS1021-2*4SF11-B")
      (footprint "PLD2-4")
      (description "Вилка штыревая 2.54мм 2x4 прямая тип1")
      (libsource (lib "MyCompLib") (part "DS1021_2x4"))
    )
    (comp (ref "X10")
      (value "DS1021_1x4")
      (footprint "PLD1X4")
      (description "Вилка штыревая 2.54мм 1x4 прямая тип1")
      (libsource (lib "MyCompLib") (part "DS1021_1x4"))
    )
    (comp (ref "X11")
      (value "B16B-PHDSS")
      (footprint "PHD16")
      (description "HEADER, PHD, TOP, 16WAY, 2MM; Pitch Spacing:2mm; No. of Contacts:16Contacts;")
      (libsource (lib "MyCompLib") (part "B16B-PHDSS"))
    )
    (comp (ref "X12")
      (value "TRJ0011TBNL (J0011D018)")
      (footprint "J0011D018")
      (description "Conn RJ-45 F 8 POS 2.54mm Solder RA Thru-Hole 12 Terminal 1 Port Cat 5/Cat 6")
      (libsource (lib "MyCompLib") (part "RJ45 J0011D018"))
    )
  )
  (nets
    (net (code "1") (name "/50MHz") (class "Default")
      (node (ref "BQ3") (pin "3") (pinfunction "OUT_3") (pintype "passive"))
      (node (ref "D10") (pin "34") (pinfunction "X1_34") (pintype "input"))
      (node (ref "D8") (pin "24") (pinfunction "PA1_24") (pintype "bidirectional"))
    )
    (net (code "2") (name "/BOOT0") (class "Default")
      (node (ref "R29") (pin "2") (pinfunction "2_2") (pintype "passive"))
      (node (ref "X8") (pin "4") (pinfunction "4_4") (pintype "passive"))
    )
    (net (code "3") (name "/BOOT1") (class "Default")
      (node (ref "R28") (pin "2") (pinfunction "2_2") (pintype "passive"))
      (node (ref "X8") (pin "3") (pinfunction "3_3") (pintype "passive"))
    )
    (net (code "4") (name "/BUZZ") (class "Default")
      (node (ref "D8") (pin "26") (pinfunction "PA3_26") (pintype "bidirectional"))
      (node (ref "R39") (pin "1") (pinfunction "1_1") (pintype "passive"))
    )
    (net (code "5") (name "/CAN1_Rx") (class "Default")
      (node (ref "D3") (pin "4") (pinfunction "R_4") (pintype "output"))
      (node (ref "D8") (pin "70") (pinfunction "PA11_70") (pintype "bidirectional"))
    )
    (net (code "6") (name "/CAN1_Tx") (class "Default")
      (node (ref "D3") (pin "1") (pinfunction "D_1") (pintype "input"))
      (node (ref "D8") (pin "71") (pinfunction "PA12_71") (pintype "bidirectional"))
    )
    (net (code "7") (name "/CAN_N") (class "Default")
      (node (ref "D3") (pin "6") (pinfunction "CANL_6") (pintype "output"))
      (node (ref "R9") (pin "1") (pinfunction "1_1") (pintype "passive"))
      (node (ref "VD5") (pin "4") (pinfunction "C_4") (pintype "passive"))
      (node (ref "X5") (pin "2") (pinfunction "2_2") (pintype "passive"))
    )
    (net (code "8") (name "/CAN_P") (class "Default")
      (node (ref "D3") (pin "7") (pinfunction "CANH_7") (pintype "output"))
      (node (ref "VD5") (pin "3") (pinfunction "B_3") (pintype "passive"))
      (node (ref "X3") (pin "2") (pinfunction "2_2") (pintype "passive"))
      (node (ref "X5") (pin "7") (pinfunction "7_7") (pintype "passive"))
    )
    (net (code "9") (name "/CAN_Rs") (class "Default")
      (node (ref "D8") (pin "43") (pinfunction "PE12_43") (pintype "bidirectional"))
      (node (ref "R3") (pin "2") (pinfunction "2_2") (pintype "passive"))
    )
    (net (code "10") (name "/EEP_CS") (class "Default")
      (node (ref "D2") (pin "1") (pinfunction "S_1") (pintype "passive"))
      (node (ref "D8") (pin "39") (pinfunction "PE8_39") (pintype "bidirectional"))
      (node (ref "R1") (pin "1") (pinfunction "1_1") (pintype "passive"))
    )
    (net (code "11") (name "/E_MDC") (class "Default")
      (node (ref "D10") (pin "31") (pinfunction "MDC_31") (pintype "input"))
      (node (ref "D8") (pin "16") (pinfunction "PC1_16") (pintype "bidirectional"))
    )
    (net (code "12") (name "/E_MDIO") (class "Default")
      (node (ref "D10") (pin "30") (pinfunction "MDIO_30") (pintype "bidirectional"))
      (node (ref "D8") (pin "25") (pinfunction "PA2_25") (pintype "bidirectional"))
      (node (ref "R45") (pin "1") (pinfunction "1_1") (pintype "passive"))
    )
    (net (code "13") (name "/E_NRST") (class "Default")
      (node (ref "D10") (pin "29") (pinfunction "RESET_29") (pintype "input"))
      (node (ref "D8") (pin "47") (pinfunction "PB10_47") (pintype "bidirectional"))
    )
    (net (code "14") (name "/E_RMII_CRSDV") (class "Default")
      (node (ref "D10") (pin "40") (pinfunction "CRS/CRS_DV/LED_CFG_40") (pintype "output"))
      (node (ref "D8") (pin "32") (pinfunction "PA7_32") (pintype "bidirectional"))
      (node (ref "R49") (pin "1") (pinfunction "1_1") (pintype "passive"))
    )
    (net (code "15") (name "/E_RXD0") (class "Default")
      (node (ref "D10") (pin "43") (pinfunction "RXD_0/PHYAD1_43") (pintype "output"))
      (node (ref "D8") (pin "33") (pinfunction "PC4_33") (pintype "bidirectional"))
    )
    (net (code "16") (name "/E_RXD1") (class "Default")
      (node (ref "D10") (pin "44") (pinfunction "RXD_1/PHYAD2_44") (pintype "output"))
      (node (ref "D8") (pin "34") (pinfunction "PC5_34") (pintype "bidirectional"))
    )
    (net (code "17") (name "/E_TXD0") (class "Default")
      (node (ref "D10") (pin "3") (pinfunction "TXD_0_3") (pintype "input"))
      (node (ref "D8") (pin "51") (pinfunction "PB12_51") (pintype "bidirectional"))
    )
    (net (code "18") (name "/E_TXD1") (class "Default")
      (node (ref "D10") (pin "4") (pinfunction "TXD_1_4") (pintype "input"))
      (node (ref "D8") (pin "52") (pinfunction "PB13_52") (pintype "bidirectional"))
    )
    (net (code "19") (name "/E_TXEN") (class "Default")
      (node (ref "D10") (pin "2") (pinfunction "TX_EN_2") (pintype "input"))
      (node (ref "D8") (pin "48") (pinfunction "PB11_48") (pintype "bidirectional"))
    )
    (net (code "20") (name "/FL_CSS") (class "Default")
      (node (ref "D1") (pin "4") (pinfunction "CS_4") (pintype "power_in"))
      (node (ref "D8") (pin "35") (pinfunction "PB0_35") (pintype "bidirectional"))
      (node (ref "R2") (pin "1") (pinfunction "1_1") (pintype "passive"))
    )
    (net (code "21") (name "/I2C1_SCL") (class "Default")
      (node (ref "D8") (pin "95") (pinfunction "PB8_95") (pintype "bidirectional"))
      (node (ref "R67") (pin "1") (pinfunction "1_1") (pintype "passive"))
      (node (ref "X11") (pin "4") (pinfunction "4_4") (pintype "passive"))
    )
    (net (code "22") (name "/I2C1_SDA") (class "Default")
      (node (ref "D8") (pin "96") (pinfunction "PB9_96") (pintype "bidirectional"))
      (node (ref "R60") (pin "1") (pinfunction "1_1") (pintype "passive"))
      (node (ref "X11") (pin "5") (pinfunction "5_5") (pintype "passive"))
    )
    (net (code "23") (name "/JDTI") (class "Default")
      (node (ref "D8") (pin "77") (pinfunction "PA15(JTDI)_77") (pintype "bidirectional"))
      (node (ref "R37") (pin "1") (pinfunction "1_1") (pintype "passive"))
      (node (ref "X9") (pin "7") (pinfunction "7_7") (pintype "passive"))
    )
    (net (code "24") (name "/LED1") (class "Default")
      (node (ref "D8") (pin "3") (pinfunction "PE4_3") (pintype "bidirectional"))
      (node (ref "HL6") (pin "2") (pinfunction "K_2") (pintype "passive"))
    )
    (net (code "25") (name "/LED2") (class "Default")
      (node (ref "D8") (pin "2") (pinfunction "PE3_2") (pintype "bidirectional"))
      (node (ref "HL5") (pin "2") (pinfunction "K_2") (pintype "passive"))
    )
    (net (code "26") (name "/LED3") (class "Default")
      (node (ref "D8") (pin "4") (pinfunction "PE5_4") (pintype "bidirectional"))
      (node (ref "HL4") (pin "2") (pinfunction "K_2") (pintype "passive"))
    )
    (net (code "27") (name "/LED_ACT") (class "Default")
      (node (ref "D10") (pin "26") (pinfunction "LED_ACT/COL/AN_EN_26") (pintype "output"))
      (node (ref "R48") (pin "1") (pinfunction "1_1") (pintype "passive"))
      (node (ref "X12") (pin "11") (pinfunction "RC_11") (pintype "passive"))
    )
    (net (code "28") (name "/LED_LINK") (class "Default")
      (node (ref "D10") (pin "28") (pinfunction "LED_LINK/AN0_28") (pintype "output"))
      (node (ref "R50") (pin "1") (pinfunction "1_1") (pintype "passive"))
      (node (ref "X12") (pin "10") (pinfunction "LC_10") (pintype "passive"))
    )
    (net (code "29") (name "/MISO") (class "Default")
      (node (ref "D1") (pin "8") (pinfunction "SO_8") (pintype "power_in"))
      (node (ref "D2") (pin "2") (pinfunction "Q_2") (pintype "passive"))
      (node (ref "D8") (pin "31") (pinfunction "PA6_31") (pintype "bidirectional"))
      (node (ref "X11") (pin "10") (pinfunction "10_10") (pintype "passive"))
    )
    (net (code "30") (name "/MOSI") (class "Default")
      (node (ref "D1") (pin "1") (pinfunction "SI_1") (pintype "passive"))
      (node (ref "D2") (pin "5") (pinfunction "D_5") (pintype "passive"))
      (node (ref "D8") (pin "91") (pinfunction "PB5_91") (pintype "bidirectional"))
      (node (ref "X11") (pin "7") (pinfunction "7_7") (pintype "passive"))
    )
    (net (code "31") (name "/NJRST") (class "Default")
      (node (ref "D8") (pin "90") (pinfunction "PB4(NJTRST)_90") (pintype "bidirectional"))
      (node (ref "R36") (pin "1") (pinfunction "1_1") (pintype "passive"))
      (node (ref "X9") (pin "5") (pinfunction "5_5") (pintype "passive"))
    )
    (net (code "32") (name "/NRST") (class "Default")
      (node (ref "C36") (pin "1") (pinfunction "1_1") (pintype "passive"))
      (node (ref "D8") (pin "14") (pinfunction "NRST_14") (pintype "bidirectional"))
      (node (ref "R31") (pin "1") (pinfunction "1_1") (pintype "passive"))
      (node (ref "S1") (pin "1") (pinfunction "1_1") (pintype "passive"))
    )
    (net (code "33") (name "/PD3") (class "Default")
      (node (ref "D8") (pin "84") (pinfunction "PD3_84") (pintype "bidirectional"))
      (node (ref "X11") (pin "1") (pinfunction "1_1") (pintype "passive"))
    )
    (net (code "34") (name "/PD4") (class "Default")
      (node (ref "D8") (pin "85") (pinfunction "PD4_85") (pintype "bidirectional"))
      (node (ref "X11") (pin "2") (pinfunction "2_2") (pintype "passive"))
    )
    (net (code "35") (name "/PD7") (class "Default")
      (node (ref "D8") (pin "88") (pinfunction "PD7_88") (pintype "bidirectional"))
      (node (ref "X11") (pin "3") (pinfunction "3_3") (pintype "passive"))
    )
    (net (code "36") (name "/PE0") (class "Default")
      (node (ref "D8") (pin "97") (pinfunction "PE0_97") (pintype "bidirectional"))
      (node (ref "X11") (pin "6") (pinfunction "6_6") (pintype "passive"))
    )
    (net (code "37") (name "/PFB") (class "Default")
      (node (ref "C46") (pin "1") (pinfunction "1_1") (pintype "passive"))
      (node (ref "C47") (pin "1") (pinfunction "1_1") (pintype "passive"))
      (node (ref "C52") (pin "1") (pinfunction "1_1") (pintype "passive"))
      (node (ref "C54") (pin "1") (pinfunction "1_1") (pintype "passive"))
      (node (ref "D10") (pin "18") (pinfunction "PFBIN1_18") (pintype "input"))
      (node (ref "D10") (pin "23") (pinfunction "PFBOUT_23") (pintype "output"))
      (node (ref "D10") (pin "37") (pinfunction "PFBIN2_37") (pintype "input"))
    )
    (net (code "38") (name "/RD_N") (class "Default")
      (node (ref "D10") (pin "13") (pinfunction "RD-_13") (pintype "bidirectional"))
      (node (ref "R65") (pin "1") (pinfunction "1_1") (pintype "passive"))
      (node (ref "VD8") (pin "5") (pinfunction "D_5") (pintype "passive"))
      (node (ref "X12") (pin "6") (pinfunction "RD-_6") (pintype "passive"))
    )
    (net (code "39") (name "/RD_P") (class "Default")
      (node (ref "D10") (pin "14") (pinfunction "RD+_14") (pintype "bidirectional"))
      (node (ref "R63") (pin "1") (pinfunction "1_1") (pintype "passive"))
      (node (ref "VD8") (pin "4") (pinfunction "B_4") (pintype "passive"))
      (node (ref "X12") (pin "3") (pinfunction "RD+_3") (pintype "passive"))
    )
    (net (code "40") (name "/RS485_Cntr") (class "Default")
      (node (ref "D6") (pin "2") (pinfunction "RE_2") (pintype "passive"))
      (node (ref "D6") (pin "3") (pinfunction "DE_3") (pintype "passive"))
      (node (ref "D8") (pin "1") (pinfunction "PE2_1") (pintype "bidirectional"))
      (node (ref "R11") (pin "2") (pinfunction "2_2") (pintype "passive"))
    )
    (net (code "41") (name "/RS485_N") (class "Default")
      (node (ref "D6") (pin "6") (pinfunction "A_6") (pintype "passive"))
      (node (ref "R22") (pin "2") (pinfunction "2_2") (pintype "passive"))
      (node (ref "X6") (pin "2") (pinfunction "2_2") (pintype "passive"))
      (node (ref "X7") (pin "4") (pinfunction "4_4") (pintype "passive"))
    )
    (net (code "42") (name "/RS485_P") (class "Default")
      (node (ref "D6") (pin "7") (pinfunction "B_7") (pintype "passive"))
      (node (ref "D9") (pin "13") (pinfunction "R1IN_13") (pintype "passive"))
      (node (ref "R20") (pin "1") (pinfunction "1_1") (pintype "passive"))
      (node (ref "R21") (pin "2") (pinfunction "2_2") (pintype "passive"))
      (node (ref "X7") (pin "3") (pinfunction "3_3") (pintype "passive"))
    )
    (net (code "43") (name "/RX2") (class "Default")
      (node (ref "D6") (pin "1") (pinfunction "RO_1") (pintype "passive"))
      (node (ref "D8") (pin "87") (pinfunction "PD6_87") (pintype "bidirectional"))
      (node (ref "D9") (pin "12") (pinfunction "R1OUT_12") (pintype "passive"))
      (node (ref "R10") (pin "1") (pinfunction "1_1") (pintype "passive"))
    )
    (net (code "44") (name "/SCK") (class "Default")
      (node (ref "D1") (pin "2") (pinfunction "SCK_2") (pintype "passive"))
      (node (ref "D2") (pin "6") (pinfunction "C_6") (pintype "passive"))
      (node (ref "D8") (pin "30") (pinfunction "PA5_30") (pintype "bidirectional"))
      (node (ref "R5") (pin "2") (pinfunction "2_2") (pintype "passive"))
      (node (ref "X11") (pin "9") (pinfunction "9_9") (pintype "passive"))
    )
    (net (code "45") (name "/SDIO_CLK") (class "Default")
      (node (ref "D8") (pin "80") (pinfunction "PC12_80") (pintype "bidirectional"))
      (node (ref "R18") (pin "1") (pinfunction "1_1") (pintype "passive"))
      (node (ref "X4") (pin "5") (pinfunction "CLK_5") (pintype "passive"))
    )
    (net (code "46") (name "/SDIO_CMD") (class "Default")
      (node (ref "D8") (pin "83") (pinfunction "PD2_83") (pintype "bidirectional"))
      (node (ref "R17") (pin "1") (pinfunction "1_1") (pintype "passive"))
      (node (ref "X4") (pin "3") (pinfunction "CMD_3") (pintype "passive"))
    )
    (net (code "47") (name "/SDIO_D0") (class "Default")
      (node (ref "D8") (pin "65") (pinfunction "PC8_65") (pintype "bidirectional"))
      (node (ref "R12") (pin "1") (pinfunction "1_1") (pintype "passive"))
      (node (ref "X4") (pin "7") (pinfunction "D0_7") (pintype "passive"))
    )
    (net (code "48") (name "/SDIO_D1") (class "Default")
      (node (ref "D8") (pin "66") (pinfunction "PC9_66") (pintype "bidirectional"))
      (node (ref "R13") (pin "1") (pinfunction "1_1") (pintype "passive"))
      (node (ref "X4") (pin "8") (pinfunction "D1_8") (pintype "passive"))
    )
    (net (code "49") (name "/SDIO_D2") (class "Default")
      (node (ref "D8") (pin "78") (pinfunction "PC10_78") (pintype "bidirectional"))
      (node (ref "R14") (pin "1") (pinfunction "1_1") (pintype "passive"))
      (node (ref "X4") (pin "1") (pinfunction "D2_1") (pintype "passive"))
    )
    (net (code "50") (name "/SDIO_D3") (class "Default")
      (node (ref "D8") (pin "79") (pinfunction "PC11_79") (pintype "bidirectional"))
      (node (ref "R15") (pin "1") (pinfunction "1_1") (pintype "passive"))
      (node (ref "X4") (pin "2") (pinfunction "D3_2") (pintype "passive"))
    )
    (net (code "51") (name "/SWCLK") (class "Default")
      (node (ref "D8") (pin "76") (pinfunction "PA14(JTCK-SWCLK)_76") (pintype "bidirectional"))
      (node (ref "R41") (pin "2") (pinfunction "2_2") (pintype "passive"))
      (node (ref "X9") (pin "4") (pinfunction "4_4") (pintype "passive"))
    )
    (net (code "52") (name "/SWDIO") (class "Default")
      (node (ref "D8") (pin "72") (pinfunction "PA13(JTMS-SWDIO)_72") (pintype "bidirectional"))
      (node (ref "R38") (pin "1") (pinfunction "1_1") (pintype "passive"))
      (node (ref "X9") (pin "2") (pinfunction "2_2") (pintype "passive"))
    )
    (net (code "53") (name "/SWITCH1") (class "Default")
      (node (ref "D8") (pin "64") (pinfunction "PC7_64") (pintype "bidirectional"))
      (node (ref "R54") (pin "1") (pinfunction "1_1") (pintype "passive"))
      (node (ref "S2") (pin "1") (pinfunction "1_1") (pintype "passive"))
    )
    (net (code "54") (name "/SWITCH2") (class "Default")
      (node (ref "D8") (pin "63") (pinfunction "PC6_63") (pintype "bidirectional"))
      (node (ref "R55") (pin "1") (pinfunction "1_1") (pintype "passive"))
      (node (ref "S2") (pin "2") (pinfunction "2_2") (pintype "passive"))
    )
    (net (code "55") (name "/SWITCH3") (class "Default")
      (node (ref "D8") (pin "62") (pinfunction "PD15_62") (pintype "bidirectional"))
      (node (ref "R56") (pin "1") (pinfunction "1_1") (pintype "passive"))
      (node (ref "S2") (pin "3") (pinfunction "3_3") (pintype "passive"))
    )
    (net (code "56") (name "/SWITCH4") (class "Default")
      (node (ref "D8") (pin "61") (pinfunction "PD14_61") (pintype "bidirectional"))
      (node (ref "R57") (pin "1") (pinfunction "1_1") (pintype "passive"))
      (node (ref "S2") (pin "4") (pinfunction "4_4") (pintype "passive"))
    )
    (net (code "57") (name "/SWITCH5") (class "Default")
      (node (ref "D8") (pin "60") (pinfunction "PD13_60") (pintype "bidirectional"))
      (node (ref "R59") (pin "1") (pinfunction "1_1") (pintype "passive"))
      (node (ref "S2") (pin "5") (pinfunction "5_5") (pintype "passive"))
    )
    (net (code "58") (name "/SWITCH6") (class "Default")
      (node (ref "D8") (pin "59") (pinfunction "PD12_59") (pintype "bidirectional"))
      (node (ref "R62") (pin "1") (pinfunction "1_1") (pintype "passive"))
      (node (ref "S2") (pin "6") (pinfunction "6_6") (pintype "passive"))
    )
    (net (code "59") (name "/SWITCH7") (class "Default")
      (node (ref "D8") (pin "58") (pinfunction "PD11_58") (pintype "bidirectional"))
      (node (ref "R64") (pin "1") (pinfunction "1_1") (pintype "passive"))
      (node (ref "S2") (pin "7") (pinfunction "7_7") (pintype "passive"))
    )
    (net (code "60") (name "/SWITCH8") (class "Default")
      (node (ref "D8") (pin "57") (pinfunction "PD10_57") (pintype "bidirectional"))
      (node (ref "R66") (pin "1") (pinfunction "1_1") (pintype "passive"))
      (node (ref "S2") (pin "8") (pinfunction "8_8") (pintype "passive"))
    )
    (net (code "61") (name "/SWO") (class "Default")
      (node (ref "D8") (pin "89") (pinfunction "PB3(JTDO/TRACESWO)_89") (pintype "bidirectional"))
      (node (ref "R40") (pin "1") (pinfunction "1_1") (pintype "passive"))
      (node (ref "X9") (pin "6") (pinfunction "6_6") (pintype "passive"))
    )
    (net (code "62") (name "/TD_N") (class "Default")
      (node (ref "D10") (pin "16") (pinfunction "TD-_16") (pintype "bidirectional"))
      (node (ref "R61") (pin "1") (pinfunction "1_1") (pintype "passive"))
      (node (ref "VD8") (pin "3") (pinfunction "C_3") (pintype "passive"))
      (node (ref "X12") (pin "2") (pinfunction "TD-_2") (pintype "passive"))
    )
    (net (code "63") (name "/TD_P") (class "Default")
      (node (ref "D10") (pin "17") (pinfunction "TD+_17") (pintype "bidirectional"))
      (node (ref "R58") (pin "1") (pinfunction "1_1") (pintype "passive"))
      (node (ref "VD8") (pin "1") (pinfunction "A_1") (pintype "passive"))
      (node (ref "X12") (pin "1") (pinfunction "TD+_1") (pintype "passive"))
    )
    (net (code "64") (name "/TX2") (class "Default")
      (node (ref "D6") (pin "4") (pinfunction "DI_4") (pintype "power_in"))
      (node (ref "D8") (pin "86") (pinfunction "PD5_86") (pintype "bidirectional"))
      (node (ref "D9") (pin "11") (pinfunction "T1IN_11") (pintype "passive"))
    )
    (net (code "65") (name "/TxD") (class "Default")
      (node (ref "D9") (pin "14") (pinfunction "T1OUT_14") (pintype "passive"))
      (node (ref "X7") (pin "2") (pinfunction "2_2") (pintype "passive"))
    )
    (net (code "66") (name "/USART1_Rx") (class "Default")
      (node (ref "D4") (pin "1") (pinfunction "TXD_1") (pintype "output"))
      (node (ref "D8") (pin "69") (pinfunction "PA10_69") (pintype "bidirectional"))
      (node (ref "R16") (pin "1") (pinfunction "1_1") (pintype "passive"))
    )
    (net (code "67") (name "/USART1_Tx") (class "Default")
      (node (ref "D4") (pin "4") (pinfunction "RXD_4") (pintype "input"))
      (node (ref "D8") (pin "68") (pinfunction "PA9_68") (pintype "bidirectional"))
      (node (ref "R19") (pin "1") (pinfunction "1_1") (pintype "passive"))
    )
    (net (code "68") (name "/USART3_Rx") (class "Default")
      (node (ref "D8") (pin "56") (pinfunction "PD9_56") (pintype "bidirectional"))
      (node (ref "X10") (pin "3") (pinfunction "3_3") (pintype "passive"))
    )
    (net (code "69") (name "/USART3_Tx") (class "Default")
      (node (ref "D8") (pin "55") (pinfunction "PD8_55") (pintype "bidirectional"))
      (node (ref "X10") (pin "2") (pinfunction "2_2") (pintype "passive"))
    )
    (net (code "70") (name "/USB_N") (class "Default")
      (node (ref "C5") (pin "2") (pinfunction "2_2") (pintype "passive"))
      (node (ref "D4") (pin "9") (pinfunction "USBDM_9") (pintype "input"))
      (node (ref "R7") (pin "1") (pinfunction "1_1") (pintype "passive"))
      (node (ref "R7") (pin "2") (pinfunction "2_2") (pintype "passive"))
      (node (ref "VD2") (pin "3") (pinfunction "B_3") (pintype "passive"))
      (node (ref "X1") (pin "2") (pinfunction "D-_2") (pintype "passive"))
    )
    (net (code "71") (name "/USB_P") (class "Default")
      (node (ref "C4") (pin "2") (pinfunction "2_2") (pintype "passive"))
      (node (ref "D4") (pin "8") (pinfunction "USBDP_8") (pintype "input"))
      (node (ref "R6") (pin "1") (pinfunction "1_1") (pintype "passive"))
      (node (ref "R6") (pin "2") (pinfunction "2_2") (pintype "passive"))
      (node (ref "VD2") (pin "4") (pinfunction "C_4") (pintype "passive"))
      (node (ref "X1") (pin "3") (pinfunction "D+_3") (pintype "passive"))
    )
    (net (code "72") (name "/nHOLD") (class "Default")
      (node (ref "D2") (pin "7") (pinfunction "HOLD_7") (pintype "passive"))
      (node (ref "D8") (pin "29") (pinfunction "PA4_29") (pintype "bidirectional"))
    )
    (net (code "73") (name "/nW") (class "Default")
      (node (ref "D2") (pin "3") (pinfunction "W_3") (pintype "passive"))
      (node (ref "D8") (pin "38") (pinfunction "PE7_38") (pintype "bidirectional"))
    )
    (net (code "74") (name "3V3") (class "Default")
      (node (ref "BQ3") (pin "4") (pinfunction "+VS_4") (pintype "passive"))
      (node (ref "C10") (pin "1") (pinfunction "1_1") (pintype "passive"))
      (node (ref "C11") (pin "1") (pinfunction "1_1") (pintype "passive"))
      (node (ref "C19") (pin "1") (pinfunction "1_1") (pintype "passive"))
      (node (ref "C2") (pin "2") (pinfunction "2_2") (pintype "passive"))
      (node (ref "C20") (pin "2") (pinfunction "2_2") (pintype "passive"))
      (node (ref "C21") (pin "2") (pinfunction "2_2") (pintype "passive"))
      (node (ref "C22") (pin "2") (pinfunction "2_2") (pintype "passive"))
      (node (ref "C23") (pin "1") (pinfunction "1_1") (pintype "passive"))
      (node (ref "C24") (pin "2") (pinfunction "2_2") (pintype "passive"))
      (node (ref "C27") (pin "2") (pinfunction "2_2") (pintype "passive"))
      (node (ref "C28") (pin "2") (pinfunction "2_2") (pintype "passive"))
      (node (ref "C3") (pin "1") (pinfunction "1_1") (pintype "passive"))
      (node (ref "C33") (pin "2") (pinfunction "2_2") (pintype "passive"))
      (node (ref "C39") (pin "1") (pinfunction "1_1") (pintype "passive"))
      (node (ref "C40") (pin "1") (pinfunction "1_1") (pintype "passive"))
      (node (ref "C41") (pin "1") (pinfunction "1_1") (pintype "passive"))
      (node (ref "C42") (pin "1") (pinfunction "1_1") (pintype "passive"))
      (node (ref "C43") (pin "2") (pinfunction "2_2") (pintype "passive"))
      (node (ref "C45") (pin "2") (pinfunction "2_2") (pintype "passive"))
      (node (ref "C48") (pin "2") (pinfunction "2_2") (pintype "passive"))
      (node (ref "C49") (pin "2") (pinfunction "2_2") (pintype "passive"))
      (node (ref "C50") (pin "1") (pinfunction "1_1") (pintype "passive"))
      (node (ref "C51") (pin "1") (pinfunction "1_1") (pintype "passive"))
      (node (ref "C8") (pin "2") (pinfunction "2_2") (pintype "passive"))
      (node (ref "D1") (pin "3") (pinfunction "RESET_3") (pintype "passive"))
      (node (ref "D1") (pin "5") (pinfunction "WP_5") (pintype "passive"))
      (node (ref "D1") (pin "6") (pinfunction "VCC_6") (pintype "passive"))
      (node (ref "D10") (pin "22") (pinfunction "AVDD33_22") (pintype "power_in"))
      (node (ref "D10") (pin "32") (pinfunction "IOVDD33_2_32") (pintype "power_in"))
      (node (ref "D10") (pin "48") (pinfunction "IOVDD33_48") (pintype "power_in"))
      (node (ref "D2") (pin "8") (pinfunction "VCC_8") (pintype "power_in"))
      (node (ref "D3") (pin "3") (pinfunction "VCC_3") (pintype "power_in"))
      (node (ref "D6") (pin "8") (pinfunction "VCC_8") (pintype "power_in"))
      (node (ref "D7") (pin "2") (pinfunction "UOUT_2") (pintype "output"))
      (node (ref "D8") (pin "100") (pinfunction "VDD_100") (pintype "power_in"))
      (node (ref "D8") (pin "11") (pinfunction "VDD_11") (pintype "power_in"))
      (node (ref "D8") (pin "19") (pinfunction "VDD_19") (pintype "power_in"))
      (node (ref "D8") (pin "28") (pinfunction "VDD_28") (pintype "power_in"))
      (node (ref "D8") (pin "50") (pinfunction "VDD_50") (pintype "power_in"))
      (node (ref "D8") (pin "75") (pinfunction "VDD_75") (pintype "power_in"))
      (node (ref "D9") (pin "16") (pinfunction "VCC_16") (pintype "power_in"))
      (node (ref "L2") (pin "1") (pinfunction "1_1") (pintype "passive"))
      (node (ref "R1") (pin "2") (pinfunction "2_2") (pintype "passive"))
      (node (ref "R10") (pin "2") (pinfunction "2_2") (pintype "passive"))
      (node (ref "R12") (pin "2") (pinfunction "2_2") (pintype "passive"))
      (node (ref "R13") (pin "2") (pinfunction "2_2") (pintype "passive"))
      (node (ref "R14") (pin "2") (pinfunction "2_2") (pintype "passive"))
      (node (ref "R15") (pin "2") (pinfunction "2_2") (pintype "passive"))
      (node (ref "R17") (pin "2") (pinfunction "2_2") (pintype "passive"))
      (node (ref "R18") (pin "2") (pinfunction "2_2") (pintype "passive"))
      (node (ref "R2") (pin "2") (pinfunction "2_2") (pintype "passive"))
      (node (ref "R22") (pin "1") (pinfunction "1_1") (pintype "passive"))
      (node (ref "R31") (pin "2") (pinfunction "2_2") (pintype "passive"))
      (node (ref "R32") (pin "1") (pinfunction "1_1") (pintype "passive"))
      (node (ref "R33") (pin "1") (pinfunction "1_1") (pintype "passive"))
      (node (ref "R34") (pin "1") (pinfunction "1_1") (pintype "passive"))
      (node (ref "R35") (pin "2") (pinfunction "2_2") (pintype "passive"))
      (node (ref "R36") (pin "2") (pinfunction "2_2") (pintype "passive"))
      (node (ref "R37") (pin "2") (pinfunction "2_2") (pintype "passive"))
      (node (ref "R38") (pin "2") (pinfunction "2_2") (pintype "passive"))
      (node (ref "R40") (pin "2") (pinfunction "2_2") (pintype "passive"))
      (node (ref "R42") (pin "2") (pinfunction "2_2") (pintype "passive"))
      (node (ref "R43") (pin "2") (pinfunction "2_2") (pintype "passive"))
      (node (ref "R45") (pin "2") (pinfunction "2_2") (pintype "passive"))
      (node (ref "R46") (pin "2") (pinfunction "2_2") (pintype "passive"))
      (node (ref "R47") (pin "2") (pinfunction "2_2") (pintype "passive"))
      (node (ref "R48") (pin "2") (pinfunction "2_2") (pintype "passive"))
      (node (ref "R49") (pin "2") (pinfunction "2_2") (pintype "passive"))
      (node (ref "R50") (pin "2") (pinfunction "2_2") (pintype "passive"))
      (node (ref "R52") (pin "2") (pinfunction "2_2") (pintype "passive"))
      (node (ref "R54") (pin "2") (pinfunction "2_2") (pintype "passive"))
      (node (ref "R55") (pin "2") (pinfunction "2_2") (pintype "passive"))
      (node (ref "R56") (pin "2") (pinfunction "2_2") (pintype "passive"))
      (node (ref "R57") (pin "2") (pinfunction "2_2") (pintype "passive"))
      (node (ref "R58") (pin "2") (pinfunction "2_2") (pintype "passive"))
      (node (ref "R59") (pin "2") (pinfunction "2_2") (pintype "passive"))
      (node (ref "R60") (pin "2") (pinfunction "2_2") (pintype "passive"))
      (node (ref "R61") (pin "2") (pinfunction "2_2") (pintype "passive"))
      (node (ref "R62") (pin "2") (pinfunction "2_2") (pintype "passive"))
      (node (ref "R63") (pin "2") (pinfunction "2_2") (pintype "passive"))
      (node (ref "R64") (pin "2") (pinfunction "2_2") (pintype "passive"))
      (node (ref "R65") (pin "2") (pinfunction "2_2") (pintype "passive"))
      (node (ref "R66") (pin "2") (pinfunction "2_2") (pintype "passive"))
      (node (ref "R67") (pin "2") (pinfunction "2_2") (pintype "passive"))
      (node (ref "R69") (pin "2") (pinfunction "2_2") (pintype "passive"))
      (node (ref "R70") (pin "2") (pinfunction "2_2") (pintype "passive"))
      (node (ref "VD7") (pin "2") (pinfunction "A2_2") (pintype "passive"))
      (node (ref "X11") (pin "11") (pinfunction "11_11") (pintype "passive"))
      (node (ref "X11") (pin "12") (pinfunction "12_12") (pintype "passive"))
      (node (ref "X12") (pin "4") (pinfunction "CTT_4") (pintype "passive"))
      (node (ref "X12") (pin "5") (pinfunction "CTR_5") (pintype "passive"))
      (node (ref "X4") (pin "4") (pinfunction "3V3_4") (pintype "passive"))
      (node (ref "X5") (pin "1") (pinfunction "1_1") (pintype "passive"))
      (node (ref "X7") (pin "1") (pinfunction "1_1") (pintype "passive"))
      (node (ref "X8") (pin "1") (pinfunction "1_1") (pintype "passive"))
      (node (ref "X8") (pin "2") (pinfunction "2_2") (pintype "passive"))
      (node (ref "X9") (pin "1") (pinfunction "1_1") (pintype "passive"))
      (node (ref "X9") (pin "3") (pinfunction "3_3") (pintype "passive"))
    )
    (net (code "75") (name "5V") (class "Default")
      (node (ref "C12") (pin "2") (pinfunction "2_2") (pintype "passive"))
      (node (ref "C13") (pin "1") (pinfunction "+_1") (pintype "passive"))
      (node (ref "C14") (pin "2") (pinfunction "2_2") (pintype "passive"))
      (node (ref "C44") (pin "2") (pinfunction "2_2") (pintype "passive"))
      (node (ref "D7") (pin "3") (pinfunction "VIN_3") (pintype "bidirectional"))
      (node (ref "G1") (pin "+") (pinfunction "+_+") (pintype "passive"))
      (node (ref "L1") (pin "2") (pinfunction "2_2") (pintype "passive"))
      (node (ref "R26") (pin "2") (pinfunction "2_2") (pintype "passive"))
      (node (ref "VD4") (pin "C") (pinfunction "C_C") (pintype "passive"))
      (node (ref "X10") (pin "4") (pinfunction "4_4") (pintype "passive"))
      (node (ref "X11") (pin "13") (pinfunction "13_13") (pintype "passive"))
      (node (ref "X11") (pin "14") (pinfunction "14_14") (pintype "passive"))
      (node (ref "X5") (pin "9") (pinfunction "9_9") (pintype "passive"))
      (node (ref "X7") (pin "9") (pinfunction "9_9") (pintype "passive"))
    )
    (net (code "76") (name "GND") (class "Default")
      (node (ref "BQ3") (pin "2") (pinfunction "GND_2") (pintype "passive"))
      (node (ref "C1") (pin "1") (pinfunction "1_1") (pintype "passive"))
      (node (ref "C10") (pin "2") (pinfunction "2_2") (pintype "passive"))
      (node (ref "C11") (pin "2") (pinfunction "2_2") (pintype "passive"))
      (node (ref "C12") (pin "1") (pinfunction "1_1") (pintype "passive"))
      (node (ref "C13") (pin "2") (pinfunction "-_2") (pintype "passive"))
      (node (ref "C14") (pin "1") (pinfunction "1_1") (pintype "passive"))
      (node (ref "C15") (pin "2") (pinfunction "2_2") (pintype "passive"))
      (node (ref "C16") (pin "2") (pinfunction "2_2") (pintype "passive"))
      (node (ref "C19") (pin "2") (pinfunction "2_2") (pintype "passive"))
      (node (ref "C2") (pin "1") (pinfunction "1_1") (pintype "passive"))
      (node (ref "C21") (pin "1") (pinfunction "1_1") (pintype "passive"))
      (node (ref "C22") (pin "1") (pinfunction "1_1") (pintype "passive"))
      (node (ref "C23") (pin "2") (pinfunction "2_2") (pintype "passive"))
      (node (ref "C24") (pin "1") (pinfunction "1_1") (pintype "passive"))
      (node (ref "C25") (pin "2") (pinfunction "2_2") (pintype "passive"))
      (node (ref "C26") (pin "2") (pinfunction "2_2") (pintype "passive"))
      (node (ref "C27") (pin "1") (pinfunction "1_1") (pintype "passive"))
      (node (ref "C28") (pin "1") (pinfunction "1_1") (pintype "passive"))
      (node (ref "C29") (pin "1") (pinfunction "1_1") (pintype "passive"))
      (node (ref "C3") (pin "2") (pinfunction "2_2") (pintype "passive"))
      (node (ref "C30") (pin "2") (pinfunction "2_2") (pintype "passive"))
      (node (ref "C31") (pin "1") (pinfunction "1_1") (pintype "passive"))
      (node (ref "C32") (pin "1") (pinfunction "1_1") (pintype "passive"))
      (node (ref "C33") (pin "1") (pinfunction "1_1") (pintype "passive"))
      (node (ref "C34") (pin "1") (pinfunction "1_1") (pintype "passive"))
      (node (ref "C35") (pin "1") (pinfunction "1_1") (pintype "passive"))
      (node (ref "C36") (pin "2") (pinfunction "2_2") (pintype "passive"))
      (node (ref "C37") (pin "1") (pinfunction "1_1") (pintype "passive"))
      (node (ref "C38") (pin "2") (pinfunction "2_2") (pintype "passive"))
      (node (ref "C39") (pin "2") (pinfunction "2_2") (pintype "passive"))
      (node (ref "C4") (pin "1") (pinfunction "1_1") (pintype "passive"))
      (node (ref "C40") (pin "2") (pinfunction "2_2") (pintype "passive"))
      (node (ref "C41") (pin "2") (pinfunction "2_2") (pintype "passive"))
      (node (ref "C42") (pin "2") (pinfunction "2_2") (pintype "passive"))
      (node (ref "C43") (pin "1") (pinfunction "1_1") (pintype "passive"))
      (node (ref "C44") (pin "1") (pinfunction "1_1") (pintype "passive"))
      (node (ref "C45") (pin "1") (pinfunction "1_1") (pintype "passive"))
      (node (ref "C46") (pin "2") (pinfunction "2_2") (pintype "passive"))
      (node (ref "C47") (pin "2") (pinfunction "2_2") (pintype "passive"))
      (node (ref "C48") (pin "1") (pinfunction "1_1") (pintype "passive"))
      (node (ref "C49") (pin "1") (pinfunction "1_1") (pintype "passive"))
      (node (ref "C5") (pin "1") (pinfunction "1_1") (pintype "passive"))
      (node (ref "C50") (pin "2") (pinfunction "2_2") (pintype "passive"))
      (node (ref "C51") (pin "2") (pinfunction "2_2") (pintype "passive"))
      (node (ref "C52") (pin "2") (pinfunction "2_2") (pintype "passive"))
      (node (ref "C53") (pin "1") (pinfunction "1_1") (pintype "passive"))
      (node (ref "C54") (pin "2") (pinfunction "2_2") (pintype "passive"))
      (node (ref "C6") (pin "1") (pinfunction "1_1") (pintype "passive"))
      (node (ref "C7") (pin "2") (pinfunction "-_2") (pintype "passive"))
      (node (ref "C8") (pin "1") (pinfunction "1_1") (pintype "passive"))
      (node (ref "C9") (pin "1") (pinfunction "1_1") (pintype "passive"))
      (node (ref "D1") (pin "7") (pinfunction "GND_7") (pintype "passive"))
      (node (ref "D10") (pin "15") (pinfunction "AGND_2_15") (pintype "passive"))
      (node (ref "D10") (pin "19") (pinfunction "AGND_19") (pintype "passive"))
      (node (ref "D10") (pin "35") (pinfunction "IOGND_2_35") (pintype "passive"))
      (node (ref "D10") (pin "36") (pinfunction "DGND_36") (pintype "passive"))
      (node (ref "D10") (pin "47") (pinfunction "IOGND_47") (pintype "passive"))
      (node (ref "D10") (pin "49") (pinfunction "EPAD_49") (pintype "passive"))
      (node (ref "D2") (pin "4") (pinfunction "VSS_4") (pintype "power_in"))
      (node (ref "D3") (pin "2") (pinfunction "GND_2") (pintype "power_in"))
      (node (ref "D4") (pin "13") (pinfunction "GND@1_13") (pintype "power_in"))
      (node (ref "D4") (pin "5") (pinfunction "GND_5") (pintype "power_in"))
      (node (ref "D5") (pin "3") (pinfunction "GND_2_3") (pintype "passive"))
      (node (ref "D5") (pin "5") (pinfunction "~{ON}/OFF_5") (pintype "input"))
      (node (ref "D5") (pin "6") (pinfunction "GND_6") (pintype "passive"))
      (node (ref "D6") (pin "5") (pinfunction "GND_5") (pintype "passive"))
      (node (ref "D7") (pin "1") (pinfunction "GND_1") (pintype "passive"))
      (node (ref "D8") (pin "10") (pinfunction "VSS_10") (pintype "power_in"))
      (node (ref "D8") (pin "20") (pinfunction "VSSA_20") (pintype "power_in"))
      (node (ref "D8") (pin "27") (pinfunction "VSS_27") (pintype "power_in"))
      (node (ref "D8") (pin "74") (pinfunction "VSS_74") (pintype "power_in"))
      (node (ref "D8") (pin "99") (pinfunction "VSS_99") (pintype "power_in"))
      (node (ref "D9") (pin "15") (pinfunction "GND_15") (pintype "passive"))
      (node (ref "HL1") (pin "2") (pinfunction "K_2") (pintype "passive"))
      (node (ref "J1") (pin "3") (pinfunction "NEG_3") (pintype "passive"))
      (node (ref "R11") (pin "1") (pinfunction "1_1") (pintype "passive"))
      (node (ref "R20") (pin "2") (pinfunction "2_2") (pintype "passive"))
      (node (ref "R25") (pin "1") (pinfunction "1_1") (pintype "passive"))
      (node (ref "R41") (pin "1") (pinfunction "1_1") (pintype "passive"))
      (node (ref "R5") (pin "1") (pinfunction "1_1") (pintype "passive"))
      (node (ref "R53") (pin "2") (pinfunction "2_2") (pintype "passive"))
      (node (ref "R68") (pin "1") (pinfunction "1_1") (pintype "passive"))
      (node (ref "S1") (pin "2") (pinfunction "2_2") (pintype "passive"))
      (node (ref "S2") (pin "10") (pinfunction "10_10") (pintype "passive"))
      (node (ref "S2") (pin "11") (pinfunction "11_11") (pintype "passive"))
      (node (ref "S2") (pin "12") (pinfunction "12_12") (pintype "passive"))
      (node (ref "S2") (pin "13") (pinfunction "13_13") (pintype "passive"))
      (node (ref "S2") (pin "14") (pinfunction "14_14") (pintype "passive"))
      (node (ref "S2") (pin "15") (pinfunction "15_15") (pintype "passive"))
      (node (ref "S2") (pin "16") (pinfunction "16_16") (pintype "passive"))
      (node (ref "S2") (pin "9") (pinfunction "9_9") (pintype "passive"))
      (node (ref "VD1") (pin "2") (pinfunction "K_2") (pintype "passive"))
      (node (ref "VD2") (pin "1") (pinfunction "GND_1") (pintype "passive"))
      (node (ref "VD5") (pin "1") (pinfunction "GND_1") (pintype "passive"))
      (node (ref "VD6") (pin "1") (pinfunction "POS_1") (pintype "passive"))
      (node (ref "VD8") (pin "2") (pinfunction "GND_2") (pintype "passive"))
      (node (ref "VT1") (pin "E") (pinfunction "E_E") (pintype "passive"))
      (node (ref "X1") (pin "5") (pinfunction "GND_5") (pintype "passive"))
      (node (ref "X10") (pin "1") (pinfunction "1_1") (pintype "passive"))
      (node (ref "X11") (pin "15") (pinfunction "15_15") (pintype "passive"))
      (node (ref "X11") (pin "16") (pinfunction "16_16") (pintype "passive"))
      (node (ref "X11") (pin "8") (pinfunction "8_8") (pintype "passive"))
      (node (ref "X12") (pin "8") (pinfunction "CG_8") (pintype "passive"))
      (node (ref "X2") (pin "2") (pinfunction "2_2") (pintype "passive"))
      (node (ref "X4") (pin "6") (pinfunction "GND_6") (pintype "passive"))
      (node (ref "X5") (pin "3") (pinfunction "3_3") (pintype "passive"))
      (node (ref "X5") (pin "5") (pinfunction "5_5") (pintype "passive"))
      (node (ref "X7") (pin "5") (pinfunction "5_5") (pintype "passive"))
      (node (ref "X8") (pin "5") (pinfunction "5_5") (pintype "passive"))
      (node (ref "X8") (pin "6") (pinfunction "6_6") (pintype "passive"))
      (node (ref "X9") (pin "8") (pinfunction "8_8") (pintype "passive"))
    )
    (net (code "77") (name "Net-(C7-+)") (class "Default")
      (node (ref "C6") (pin "2") (pinfunction "2_2") (pintype "passive"))
      (node (ref "C7") (pin "1") (pinfunction "+_1") (pintype "passive"))
      (node (ref "D5") (pin "1") (pinfunction "VIN_1") (pintype "power_in"))
      (node (ref "R8") (pin "1") (pinfunction "1_1") (pintype "passive"))
      (node (ref "VD3") (pin "2") (pinfunction "NEG_2") (pintype "passive"))
    )
    (net (code "78") (name "Net-(D3-RS)") (class "Default")
      (node (ref "D3") (pin "8") (pinfunction "RS_8") (pintype "input"))
      (node (ref "R3") (pin "1") (pinfunction "1_1") (pintype "passive"))
    )
    (net (code "79") (name "Net-(D4-CBUS1)") (class "Default")
      (node (ref "D4") (pin "14") (pinfunction "CBUS1_14") (pintype "bidirectional"))
      (node (ref "HL2") (pin "2") (pinfunction "NEG_2") (pintype "passive"))
    )
    (net (code "80") (name "Net-(D4-CBUS2)") (class "Default")
      (node (ref "D4") (pin "7") (pinfunction "CBUS2_7") (pintype "bidirectional"))
      (node (ref "HL3") (pin "2") (pinfunction "NEG_2") (pintype "passive"))
    )
    (net (code "81") (name "Net-(D5-FB)") (class "Default")
      (node (ref "D5") (pin "4") (pinfunction "FB_4") (pintype "input"))
      (node (ref "R25") (pin "2") (pinfunction "2_2") (pintype "passive"))
      (node (ref "R26") (pin "1") (pinfunction "1_1") (pintype "passive"))
    )
    (net (code "82") (name "Net-(D5-OUT)") (class "Default")
      (node (ref "D5") (pin "2") (pinfunction "OUT_2") (pintype "output"))
      (node (ref "L1") (pin "1") (pinfunction "1_1") (pintype "passive"))
      (node (ref "VD6") (pin "2") (pinfunction "NEG_2") (pintype "passive"))
    )
    (net (code "83") (name "Net-(D8A-BOOT0)") (class "Default")
      (node (ref "D8") (pin "94") (pinfunction "BOOT0_94") (pintype "input"))
      (node (ref "R29") (pin "1") (pinfunction "1_1") (pintype "passive"))
    )
    (net (code "84") (name "Net-(D8A-PB2-BOOT1(PB2))") (class "Default")
      (node (ref "D8") (pin "37") (pinfunction "PB2-BOOT1(PB2)_37") (pintype "bidirectional"))
      (node (ref "R28") (pin "1") (pinfunction "1_1") (pintype "passive"))
    )
    (net (code "85") (name "Net-(D8A-PC14-OSC32_IN(PC14))") (class "Default")
      (node (ref "BQ1") (pin "2") (pinfunction "2_2") (pintype "passive"))
      (node (ref "C15") (pin "1") (pinfunction "1_1") (pintype "passive"))
      (node (ref "D8") (pin "8") (pinfunction "PC14-OSC32_IN(PC14)_8") (pintype "bidirectional"))
    )
    (net (code "86") (name "Net-(D8A-PC15-OSC32_OUT(PC15))") (class "Default")
      (node (ref "BQ1") (pin "1") (pinfunction "1_1") (pintype "passive"))
      (node (ref "C16") (pin "1") (pinfunction "1_1") (pintype "passive"))
      (node (ref "D8") (pin "9") (pinfunction "PC15-OSC32_OUT(PC15)_9") (pintype "bidirectional"))
    )
    (net (code "87") (name "Net-(D8A-PH0-OSC_IN(PH0))") (class "Default")
      (node (ref "BQ2") (pin "2") (pinfunction "2_2") (pintype "passive"))
      (node (ref "C37") (pin "2") (pinfunction "2_2") (pintype "passive"))
      (node (ref "D8") (pin "12") (pinfunction "PH0-OSC_IN(PH0)_12") (pintype "bidirectional"))
      (node (ref "R30") (pin "2") (pinfunction "2_2") (pintype "passive"))
    )
    (net (code "88") (name "Net-(D8A-PH1-OSC_OUT(PH1))") (class "Default")
      (node (ref "BQ2") (pin "1") (pinfunction "1_1") (pintype "passive"))
      (node (ref "C38") (pin "1") (pinfunction "1_1") (pintype "passive"))
      (node (ref "D8") (pin "13") (pinfunction "PH1-OSC_OUT(PH1)_13") (pintype "bidirectional"))
      (node (ref "R30") (pin "1") (pinfunction "1_1") (pintype "passive"))
    )
    (net (code "89") (name "Net-(D8A-VCAP_1)") (class "Default")
      (node (ref "C34") (pin "2") (pinfunction "2_2") (pintype "passive"))
      (node (ref "D8") (pin "49") (pinfunction "VCAP_1_49") (pintype "power_in"))
    )
    (net (code "90") (name "Net-(D8A-VCAP_2)") (class "Default")
      (node (ref "C32") (pin "2") (pinfunction "2_2") (pintype "passive"))
      (node (ref "D8") (pin "73") (pinfunction "VCAP_2_73") (pintype "power_in"))
    )
    (net (code "91") (name "Net-(D8B-VBAT)") (class "Default")
      (node (ref "C35") (pin "2") (pinfunction "2_2") (pintype "passive"))
      (node (ref "D8") (pin "6") (pinfunction "VBAT_6") (pintype "power_in"))
      (node (ref "VD7") (pin "3") (pinfunction "C_3") (pintype "passive"))
    )
    (net (code "92") (name "Net-(D8B-VDDA)") (class "Default")
      (node (ref "C26") (pin "1") (pinfunction "1_1") (pintype "passive"))
      (node (ref "C30") (pin "1") (pinfunction "1_1") (pintype "passive"))
      (node (ref "D8") (pin "22") (pinfunction "VDDA_22") (pintype "power_in"))
      (node (ref "L2") (pin "2") (pinfunction "2_2") (pintype "passive"))
      (node (ref "R27") (pin "1") (pinfunction "1_1") (pintype "passive"))
    )
    (net (code "93") (name "Net-(D8B-VREF+)") (class "Default")
      (node (ref "C25") (pin "1") (pinfunction "1_1") (pintype "passive"))
      (node (ref "C29") (pin "2") (pinfunction "2_2") (pintype "passive"))
      (node (ref "D8") (pin "21") (pinfunction "VREF+_21") (pintype "power_in"))
      (node (ref "R27") (pin "2") (pinfunction "2_2") (pintype "passive"))
    )
    (net (code "94") (name "Net-(D9-C1+)") (class "Default")
      (node (ref "C17") (pin "1") (pinfunction "1_1") (pintype "passive"))
      (node (ref "D9") (pin "1") (pinfunction "C1+_1") (pintype "passive"))
    )
    (net (code "95") (name "Net-(D9-C1-)") (class "Default")
      (node (ref "C17") (pin "2") (pinfunction "2_2") (pintype "passive"))
      (node (ref "D9") (pin "3") (pinfunction "C1-_3") (pintype "passive"))
    )
    (net (code "96") (name "Net-(D9-C2+)") (class "Default")
      (node (ref "C18") (pin "1") (pinfunction "1_1") (pintype "passive"))
      (node (ref "D9") (pin "4") (pinfunction "C2+_4") (pintype "passive"))
    )
    (net (code "97") (name "Net-(D9-C2-)") (class "Default")
      (node (ref "C18") (pin "2") (pinfunction "2_2") (pintype "passive"))
      (node (ref "D9") (pin "5") (pinfunction "C2-_5") (pintype "passive"))
    )
    (net (code "98") (name "Net-(D9-V+)") (class "Default")
      (node (ref "C20") (pin "1") (pinfunction "1_1") (pintype "passive"))
      (node (ref "D9") (pin "2") (pinfunction "V+_2") (pintype "power_in"))
    )
    (net (code "99") (name "Net-(D9-V-)") (class "Default")
      (node (ref "C31") (pin "2") (pinfunction "2_2") (pintype "passive"))
      (node (ref "D9") (pin "6") (pinfunction "V-_6") (pintype "power_in"))
    )
    (net (code "100") (name "Net-(D10-COL{slash}PHYAD0)") (class "Default")
      (node (ref "D10") (pin "42") (pinfunction "COL/PHYAD0_42") (pintype "output"))
      (node (ref "R47") (pin "1") (pinfunction "1_1") (pintype "passive"))
    )
    (net (code "101") (name "Net-(D10-LED_SPEED{slash}AN1)") (class "Default")
      (node (ref "D10") (pin "27") (pinfunction "LED_SPEED/AN1_27") (pintype "output"))
      (node (ref "R52") (pin "1") (pinfunction "1_1") (pintype "passive"))
    )
    (net (code "102") (name "Net-(D10-PWR_DOWN{slash}INT)") (class "Default")
      (node (ref "D10") (pin "7") (pinfunction "PWR_DOWN/INT_7") (pintype "input"))
      (node (ref "R35") (pin "1") (pinfunction "1_1") (pintype "passive"))
    )
    (net (code "103") (name "Net-(D10-RBIAS)") (class "Default")
      (node (ref "D10") (pin "24") (pinfunction "RBIAS_24") (pintype "input"))
      (node (ref "R44") (pin "1") (pinfunction "1_1") (pintype "passive"))
    )
    (net (code "104") (name "Net-(D10-RESERVED)") (class "Default")
      (node (ref "D10") (pin "20") (pinfunction "RESERVED_20") (pintype "bidirectional"))
      (node (ref "R43") (pin "1") (pinfunction "1_1") (pintype "passive"))
    )
    (net (code "105") (name "Net-(D10-RESERVED_2)") (class "Default")
      (node (ref "D10") (pin "21") (pinfunction "RESERVED_2_21") (pintype "bidirectional"))
      (node (ref "R42") (pin "1") (pinfunction "1_1") (pintype "passive"))
    )
    (net (code "106") (name "Net-(D10-RX_DV{slash}MII_MODE)") (class "Default")
      (node (ref "D10") (pin "39") (pinfunction "RX_DV/MII_MODE_39") (pintype "output"))
      (node (ref "R46") (pin "1") (pinfunction "1_1") (pintype "passive"))
    )
    (net (code "107") (name "Net-(F1-Pad2)") (class "Default")
      (node (ref "F1") (pin "2") (pinfunction "2_2") (pintype "passive"))
      (node (ref "R4") (pin "1") (pinfunction "1_1") (pintype "passive"))
    )
    (net (code "108") (name "Net-(G1-Pad2)") (class "Default")
      (node (ref "G1") (pin "2") (pinfunction "2_2") (pintype "passive"))
      (node (ref "VT1") (pin "C") (pinfunction "C_C") (pintype "passive"))
    )
    (net (code "109") (name "Net-(HL1-A)") (class "Default")
      (node (ref "HL1") (pin "1") (pinfunction "A_1") (pintype "passive"))
      (node (ref "R8") (pin "2") (pinfunction "2_2") (pintype "passive"))
    )
    (net (code "110") (name "Net-(HL2-POS)") (class "Default")
      (node (ref "HL2") (pin "1") (pinfunction "POS_1") (pintype "passive"))
      (node (ref "R23") (pin "2") (pinfunction "2_2") (pintype "passive"))
    )
    (net (code "111") (name "Net-(HL3-POS)") (class "Default")
      (node (ref "HL3") (pin "1") (pinfunction "POS_1") (pintype "passive"))
      (node (ref "R24") (pin "2") (pinfunction "2_2") (pintype "passive"))
    )
    (net (code "112") (name "Net-(HL4-A)") (class "Default")
      (node (ref "HL4") (pin "1") (pinfunction "A_1") (pintype "passive"))
      (node (ref "R32") (pin "2") (pinfunction "2_2") (pintype "passive"))
    )
    (net (code "113") (name "Net-(HL5-A)") (class "Default")
      (node (ref "HL5") (pin "1") (pinfunction "A_1") (pintype "passive"))
      (node (ref "R33") (pin "2") (pinfunction "2_2") (pintype "passive"))
    )
    (net (code "114") (name "Net-(HL6-A)") (class "Default")
      (node (ref "HL6") (pin "1") (pinfunction "A_1") (pintype "passive"))
      (node (ref "R34") (pin "2") (pinfunction "2_2") (pintype "passive"))
    )
    (net (code "115") (name "Net-(R9-Pad2)") (class "Default")
      (node (ref "R9") (pin "2") (pinfunction "2_2") (pintype "passive"))
      (node (ref "X3") (pin "1") (pinfunction "1_1") (pintype "passive"))
    )
    (net (code "116") (name "Net-(R21-Pad1)") (class "Default")
      (node (ref "R21") (pin "1") (pinfunction "1_1") (pintype "passive"))
      (node (ref "X6") (pin "1") (pinfunction "1_1") (pintype "passive"))
    )
    (net (code "117") (name "Net-(R39-Pad2)") (class "Default")
      (node (ref "R39") (pin "2") (pinfunction "2_2") (pintype "passive"))
      (node (ref "VT1") (pin "B") (pinfunction "B_B") (pintype "passive"))
    )
    (net (code "118") (name "Net-(R44-Pad2)") (class "Default")
      (node (ref "R44") (pin "2") (pinfunction "2_2") (pintype "passive"))
      (node (ref "R51") (pin "1") (pinfunction "1_1") (pintype "passive"))
    )
    (net (code "119") (name "Net-(R51-Pad2)") (class "Default")
      (node (ref "R51") (pin "2") (pinfunction "2_2") (pintype "passive"))
      (node (ref "R53") (pin "1") (pinfunction "1_1") (pintype "passive"))
    )
    (net (code "120") (name "Net-(VD1-A)") (class "Default")
      (node (ref "R4") (pin "2") (pinfunction "2_2") (pintype "passive"))
      (node (ref "VD1") (pin "1") (pinfunction "A_1") (pintype "passive"))
      (node (ref "VD3") (pin "1") (pinfunction "POS_1") (pintype "passive"))
    )
    (net (code "121") (name "Net-(VD2-A)") (class "Default")
      (node (ref "F2") (pin "1") (pinfunction "1_1") (pintype "passive"))
      (node (ref "VD2") (pin "2") (pinfunction "A_2") (pintype "passive"))
      (node (ref "X1") (pin "1") (pinfunction "VBUS_1") (pintype "passive"))
    )
    (net (code "122") (name "Net-(VD7-A1)") (class "Default")
      (node (ref "J1") (pin "1") (pinfunction "POS_1") (pintype "passive"))
      (node (ref "J1") (pin "2") (pinfunction "POS_2") (pintype "passive"))
      (node (ref "VD7") (pin "1") (pinfunction "A1_1") (pintype "passive"))
    )
    (net (code "123") (name "Net-(X12-LA)") (class "Default")
      (node (ref "R69") (pin "1") (pinfunction "1_1") (pintype "passive"))
      (node (ref "X12") (pin "9") (pinfunction "LA_9") (pintype "passive"))
    )
    (net (code "124") (name "Net-(X12-RA)") (class "Default")
      (node (ref "R70") (pin "1") (pinfunction "1_1") (pintype "passive"))
      (node (ref "X12") (pin "12") (pinfunction "RA_12") (pintype "passive"))
    )
    (net (code "125") (name "SHLD") (class "Default")
      (node (ref "C53") (pin "2") (pinfunction "2_2") (pintype "passive"))
      (node (ref "R68") (pin "2") (pinfunction "2_2") (pintype "passive"))
      (node (ref "X1") (pin "6") (pinfunction "SH_6") (pintype "passive"))
      (node (ref "X1") (pin "7") (pinfunction "SH_7") (pintype "passive"))
      (node (ref "X1") (pin "8") (pinfunction "SH_8") (pintype "passive"))
      (node (ref "X1") (pin "9") (pinfunction "SH_9") (pintype "passive"))
      (node (ref "X12") (pin "S1") (pinfunction "S1_S1") (pintype "passive"))
      (node (ref "X12") (pin "S2") (pinfunction "S2_S2") (pintype "passive"))
      (node (ref "X4") (pin "10") (pinfunction "SHLD_10") (pintype "passive"))
      (node (ref "X4") (pin "11") (pinfunction "SHLD_11") (pintype "passive"))
      (node (ref "X4") (pin "12") (pinfunction "SHLD_12") (pintype "passive"))
      (node (ref "X4") (pin "9") (pinfunction "SHLD_9") (pintype "passive"))
      (node (ref "X5") (pin "10") (pinfunction "MH1_10") (pintype "passive"))
      (node (ref "X5") (pin "11") (pinfunction "MH2_11") (pintype "passive"))
      (node (ref "X7") (pin "10") (pinfunction "MH1_10") (pintype "passive"))
      (node (ref "X7") (pin "11") (pinfunction "MH2_11") (pintype "passive"))
    )
    (net (code "126") (name "VBUS") (class "Default")
      (node (ref "C1") (pin "2") (pinfunction "2_2") (pintype "passive"))
      (node (ref "D4") (pin "12") (pinfunction "VCC_12") (pintype "power_in"))
      (node (ref "F2") (pin "2") (pinfunction "2_2") (pintype "passive"))
      (node (ref "VD4") (pin "A") (pinfunction "A_A") (pintype "passive"))
    )
    (net (code "127") (name "VCC") (class "Default")
      (node (ref "F1") (pin "1") (pinfunction "1_1") (pintype "passive"))
      (node (ref "X2") (pin "1") (pinfunction "1_1") (pintype "passive"))
    )
    (net (code "128") (name "VCCIO") (class "Default")
      (node (ref "C9") (pin "2") (pinfunction "2_2") (pintype "passive"))
      (node (ref "D4") (pin "10") (pinfunction "3V3OUT_10") (pintype "output"))
      (node (ref "D4") (pin "11") (pinfunction "~{RESET}_11") (pintype "input"))
      (node (ref "D4") (pin "3") (pinfunction "VCCIO_3") (pintype "power_in"))
      (node (ref "R16") (pin "2") (pinfunction "2_2") (pintype "passive"))
      (node (ref "R19") (pin "2") (pinfunction "2_2") (pintype "passive"))
      (node (ref "R23") (pin "1") (pinfunction "1_1") (pintype "passive"))
      (node (ref "R24") (pin "1") (pinfunction "1_1") (pintype "passive"))
    )
    (net (code "129") (name "unconnected-(BQ3-STD_OP-Pad1)") (class "Default")
      (node (ref "BQ3") (pin "1") (pinfunction "STD_OP_1") (pintype "passive"))
    )
    (net (code "130") (name "unconnected-(D3-VREF-Pad5)") (class "Default")
      (node (ref "D3") (pin "5") (pinfunction "VREF_5") (pintype "output"))
    )
    (net (code "131") (name "unconnected-(D4-CBUS0-Pad15)") (class "Default")
      (node (ref "D4") (pin "15") (pinfunction "CBUS0_15") (pintype "bidirectional"))
    )
    (net (code "132") (name "unconnected-(D4-CBUS3-Pad16)") (class "Default")
      (node (ref "D4") (pin "16") (pinfunction "CBUS3_16") (pintype "bidirectional"))
    )
    (net (code "133") (name "unconnected-(D4-~{CTS}-Pad6)") (class "Default")
      (node (ref "D4") (pin "6") (pinfunction "~{CTS}_6") (pintype "input"))
    )
    (net (code "134") (name "unconnected-(D4-~{RTS}-Pad2)") (class "Default")
      (node (ref "D4") (pin "2") (pinfunction "~{RTS}_2") (pintype "output"))
    )
    (net (code "135") (name "unconnected-(D7-UOUT-Pad4)") (class "Default")
      (node (ref "D7") (pin "4") (pinfunction "UOUT_4") (pintype "output"))
    )
    (net (code "136") (name "unconnected-(D8A-PA0-WKUP(PA0)-Pad23)") (class "Default")
      (node (ref "D8") (pin "23") (pinfunction "PA0-WKUP(PA0)_23") (pintype "bidirectional"))
    )
    (net (code "137") (name "unconnected-(D8A-PA8-Pad67)") (class "Default")
      (node (ref "D8") (pin "67") (pinfunction "PA8_67") (pintype "bidirectional"))
    )
    (net (code "138") (name "unconnected-(D8A-PB1-Pad36)") (class "Default")
      (node (ref "D8") (pin "36") (pinfunction "PB1_36") (pintype "bidirectional"))
    )
    (net (code "139") (name "unconnected-(D8A-PB6-Pad92)") (class "Default")
      (node (ref "D8") (pin "92") (pinfunction "PB6_92") (pintype "bidirectional"))
    )
    (net (code "140") (name "unconnected-(D8A-PB7-Pad93)") (class "Default")
      (node (ref "D8") (pin "93") (pinfunction "PB7_93") (pintype "bidirectional"))
    )
    (net (code "141") (name "unconnected-(D8A-PB14-Pad53)") (class "Default")
      (node (ref "D8") (pin "53") (pinfunction "PB14_53") (pintype "bidirectional"))
    )
    (net (code "142") (name "unconnected-(D8A-PB15-Pad54)") (class "Default")
      (node (ref "D8") (pin "54") (pinfunction "PB15_54") (pintype "bidirectional"))
    )
    (net (code "143") (name "unconnected-(D8A-PC0-Pad15)") (class "Default")
      (node (ref "D8") (pin "15") (pinfunction "PC0_15") (pintype "bidirectional"))
    )
    (net (code "144") (name "unconnected-(D8A-PC2-Pad17)") (class "Default")
      (node (ref "D8") (pin "17") (pinfunction "PC2_17") (pintype "bidirectional"))
    )
    (net (code "145") (name "unconnected-(D8A-PC3-Pad18)") (class "Default")
      (node (ref "D8") (pin "18") (pinfunction "PC3_18") (pintype "bidirectional"))
    )
    (net (code "146") (name "unconnected-(D8A-PC13-Pad7)") (class "Default")
      (node (ref "D8") (pin "7") (pinfunction "PC13_7") (pintype "bidirectional"))
    )
    (net (code "147") (name "unconnected-(D8A-PD0-Pad81)") (class "Default")
      (node (ref "D8") (pin "81") (pinfunction "PD0_81") (pintype "bidirectional"))
    )
    (net (code "148") (name "unconnected-(D8A-PD1-Pad82)") (class "Default")
      (node (ref "D8") (pin "82") (pinfunction "PD1_82") (pintype "bidirectional"))
    )
    (net (code "149") (name "unconnected-(D8A-PE1-Pad98)") (class "Default")
      (node (ref "D8") (pin "98") (pinfunction "PE1_98") (pintype "bidirectional"))
    )
    (net (code "150") (name "unconnected-(D8A-PE6-Pad5)") (class "Default")
      (node (ref "D8") (pin "5") (pinfunction "PE6_5") (pintype "bidirectional"))
    )
    (net (code "151") (name "unconnected-(D8A-PE9-Pad40)") (class "Default")
      (node (ref "D8") (pin "40") (pinfunction "PE9_40") (pintype "bidirectional"))
    )
    (net (code "152") (name "unconnected-(D8A-PE10-Pad41)") (class "Default")
      (node (ref "D8") (pin "41") (pinfunction "PE10_41") (pintype "bidirectional"))
    )
    (net (code "153") (name "unconnected-(D8A-PE11-Pad42)") (class "Default")
      (node (ref "D8") (pin "42") (pinfunction "PE11_42") (pintype "bidirectional"))
    )
    (net (code "154") (name "unconnected-(D8A-PE13-Pad44)") (class "Default")
      (node (ref "D8") (pin "44") (pinfunction "PE13_44") (pintype "bidirectional"))
    )
    (net (code "155") (name "unconnected-(D8A-PE14-Pad45)") (class "Default")
      (node (ref "D8") (pin "45") (pinfunction "PE14_45") (pintype "bidirectional"))
    )
    (net (code "156") (name "unconnected-(D8A-PE15-Pad46)") (class "Default")
      (node (ref "D8") (pin "46") (pinfunction "PE15_46") (pintype "bidirectional"))
    )
    (net (code "157") (name "unconnected-(D9-R2IN-Pad8)") (class "Default")
      (node (ref "D9") (pin "8") (pinfunction "R2IN_8") (pintype "passive"))
    )
    (net (code "158") (name "unconnected-(D9-R2OUT-Pad9)") (class "Default")
      (node (ref "D9") (pin "9") (pinfunction "R2OUT_9") (pintype "passive"))
    )
    (net (code "159") (name "unconnected-(D9-T2IN-Pad10)") (class "Default")
      (node (ref "D9") (pin "10") (pinfunction "T2IN_10") (pintype "passive"))
    )
    (net (code "160") (name "unconnected-(D9-T2OUT-Pad7)") (class "Default")
      (node (ref "D9") (pin "7") (pinfunction "T2OUT_7") (pintype "passive"))
    )
    (net (code "161") (name "unconnected-(D10-25MHZ_OUT-Pad25)") (class "Default")
      (node (ref "D10") (pin "25") (pinfunction "25MHZ_OUT_25") (pintype "output"))
    )
    (net (code "162") (name "unconnected-(D10-RXD_2{slash}PHYAD3-Pad45)") (class "Default")
      (node (ref "D10") (pin "45") (pinfunction "RXD_2/PHYAD3_45") (pintype "output"))
    )
    (net (code "163") (name "unconnected-(D10-RXD_3{slash}PHYAD4-Pad46)") (class "Default")
      (node (ref "D10") (pin "46") (pinfunction "RXD_3/PHYAD4_46") (pintype "output"))
    )
    (net (code "164") (name "unconnected-(D10-RX_CLK-Pad38)") (class "Default")
      (node (ref "D10") (pin "38") (pinfunction "RX_CLK_38") (pintype "output"))
    )
    (net (code "165") (name "unconnected-(D10-RX_ER{slash}MDIX_EN-Pad41)") (class "Default")
      (node (ref "D10") (pin "41") (pinfunction "RX_ER/MDIX_EN_41") (pintype "output"))
    )
    (net (code "166") (name "unconnected-(D10-TCK-Pad8)") (class "Default")
      (node (ref "D10") (pin "8") (pinfunction "TCK_8") (pintype "input"))
    )
    (net (code "167") (name "unconnected-(D10-TDI-Pad12)") (class "Default")
      (node (ref "D10") (pin "12") (pinfunction "TDI_12") (pintype "input"))
    )
    (net (code "168") (name "unconnected-(D10-TDO-Pad9)") (class "Default")
      (node (ref "D10") (pin "9") (pinfunction "TDO_9") (pintype "output"))
    )
    (net (code "169") (name "unconnected-(D10-TMS-Pad10)") (class "Default")
      (node (ref "D10") (pin "10") (pinfunction "TMS_10") (pintype "input"))
    )
    (net (code "170") (name "unconnected-(D10-TRST-Pad11)") (class "Default")
      (node (ref "D10") (pin "11") (pinfunction "TRST_11") (pintype "input"))
    )
    (net (code "171") (name "unconnected-(D10-TXD_2-Pad5)") (class "Default")
      (node (ref "D10") (pin "5") (pinfunction "TXD_2_5") (pintype "input"))
    )
    (net (code "172") (name "unconnected-(D10-TXD_3{slash}SNI_MODE-Pad6)") (class "Default")
      (node (ref "D10") (pin "6") (pinfunction "TXD_3/SNI_MODE_6") (pintype "input"))
    )
    (net (code "173") (name "unconnected-(D10-TX_CLK-Pad1)") (class "Default")
      (node (ref "D10") (pin "1") (pinfunction "TX_CLK_1") (pintype "output"))
    )
    (net (code "174") (name "unconnected-(D10-X2-Pad33)") (class "Default")
      (node (ref "D10") (pin "33") (pinfunction "X2_33") (pintype "output"))
    )
    (net (code "175") (name "unconnected-(VD5-A-Pad2)") (class "Default")
      (node (ref "VD5") (pin "2") (pinfunction "A_2") (pintype "passive"))
    )
    (net (code "176") (name "unconnected-(X1-ID-Pad4)") (class "Default")
      (node (ref "X1") (pin "4") (pinfunction "ID_4") (pintype "passive"))
    )
    (net (code "177") (name "unconnected-(X5-Pad4)") (class "Default")
      (node (ref "X5") (pin "4") (pinfunction "4_4") (pintype "passive"))
    )
    (net (code "178") (name "unconnected-(X5-Pad6)") (class "Default")
      (node (ref "X5") (pin "6") (pinfunction "6_6") (pintype "passive"))
    )
    (net (code "179") (name "unconnected-(X5-Pad8)") (class "Default")
      (node (ref "X5") (pin "8") (pinfunction "8_8") (pintype "passive"))
    )
    (net (code "180") (name "unconnected-(X7-Pad6)") (class "Default")
      (node (ref "X7") (pin "6") (pinfunction "6_6") (pintype "passive"))
    )
    (net (code "181") (name "unconnected-(X7-Pad7)") (class "Default")
      (node (ref "X7") (pin "7") (pinfunction "7_7") (pintype "passive"))
    )
    (net (code "182") (name "unconnected-(X7-Pad8)") (class "Default")
      (node (ref "X7") (pin "8") (pinfunction "8_8") (pintype "passive"))
    )
    (net (code "183") (name "unconnected-(X12-NC-Pad7)") (class "Default")
      (node (ref "X12") (pin "7") (pinfunction "NC_7") (pintype "passive"))
    )
  )
)
